# Nodo_actuador_wa4_v1_b.net
KiCad netlist of a schematic drawn in EAGLE
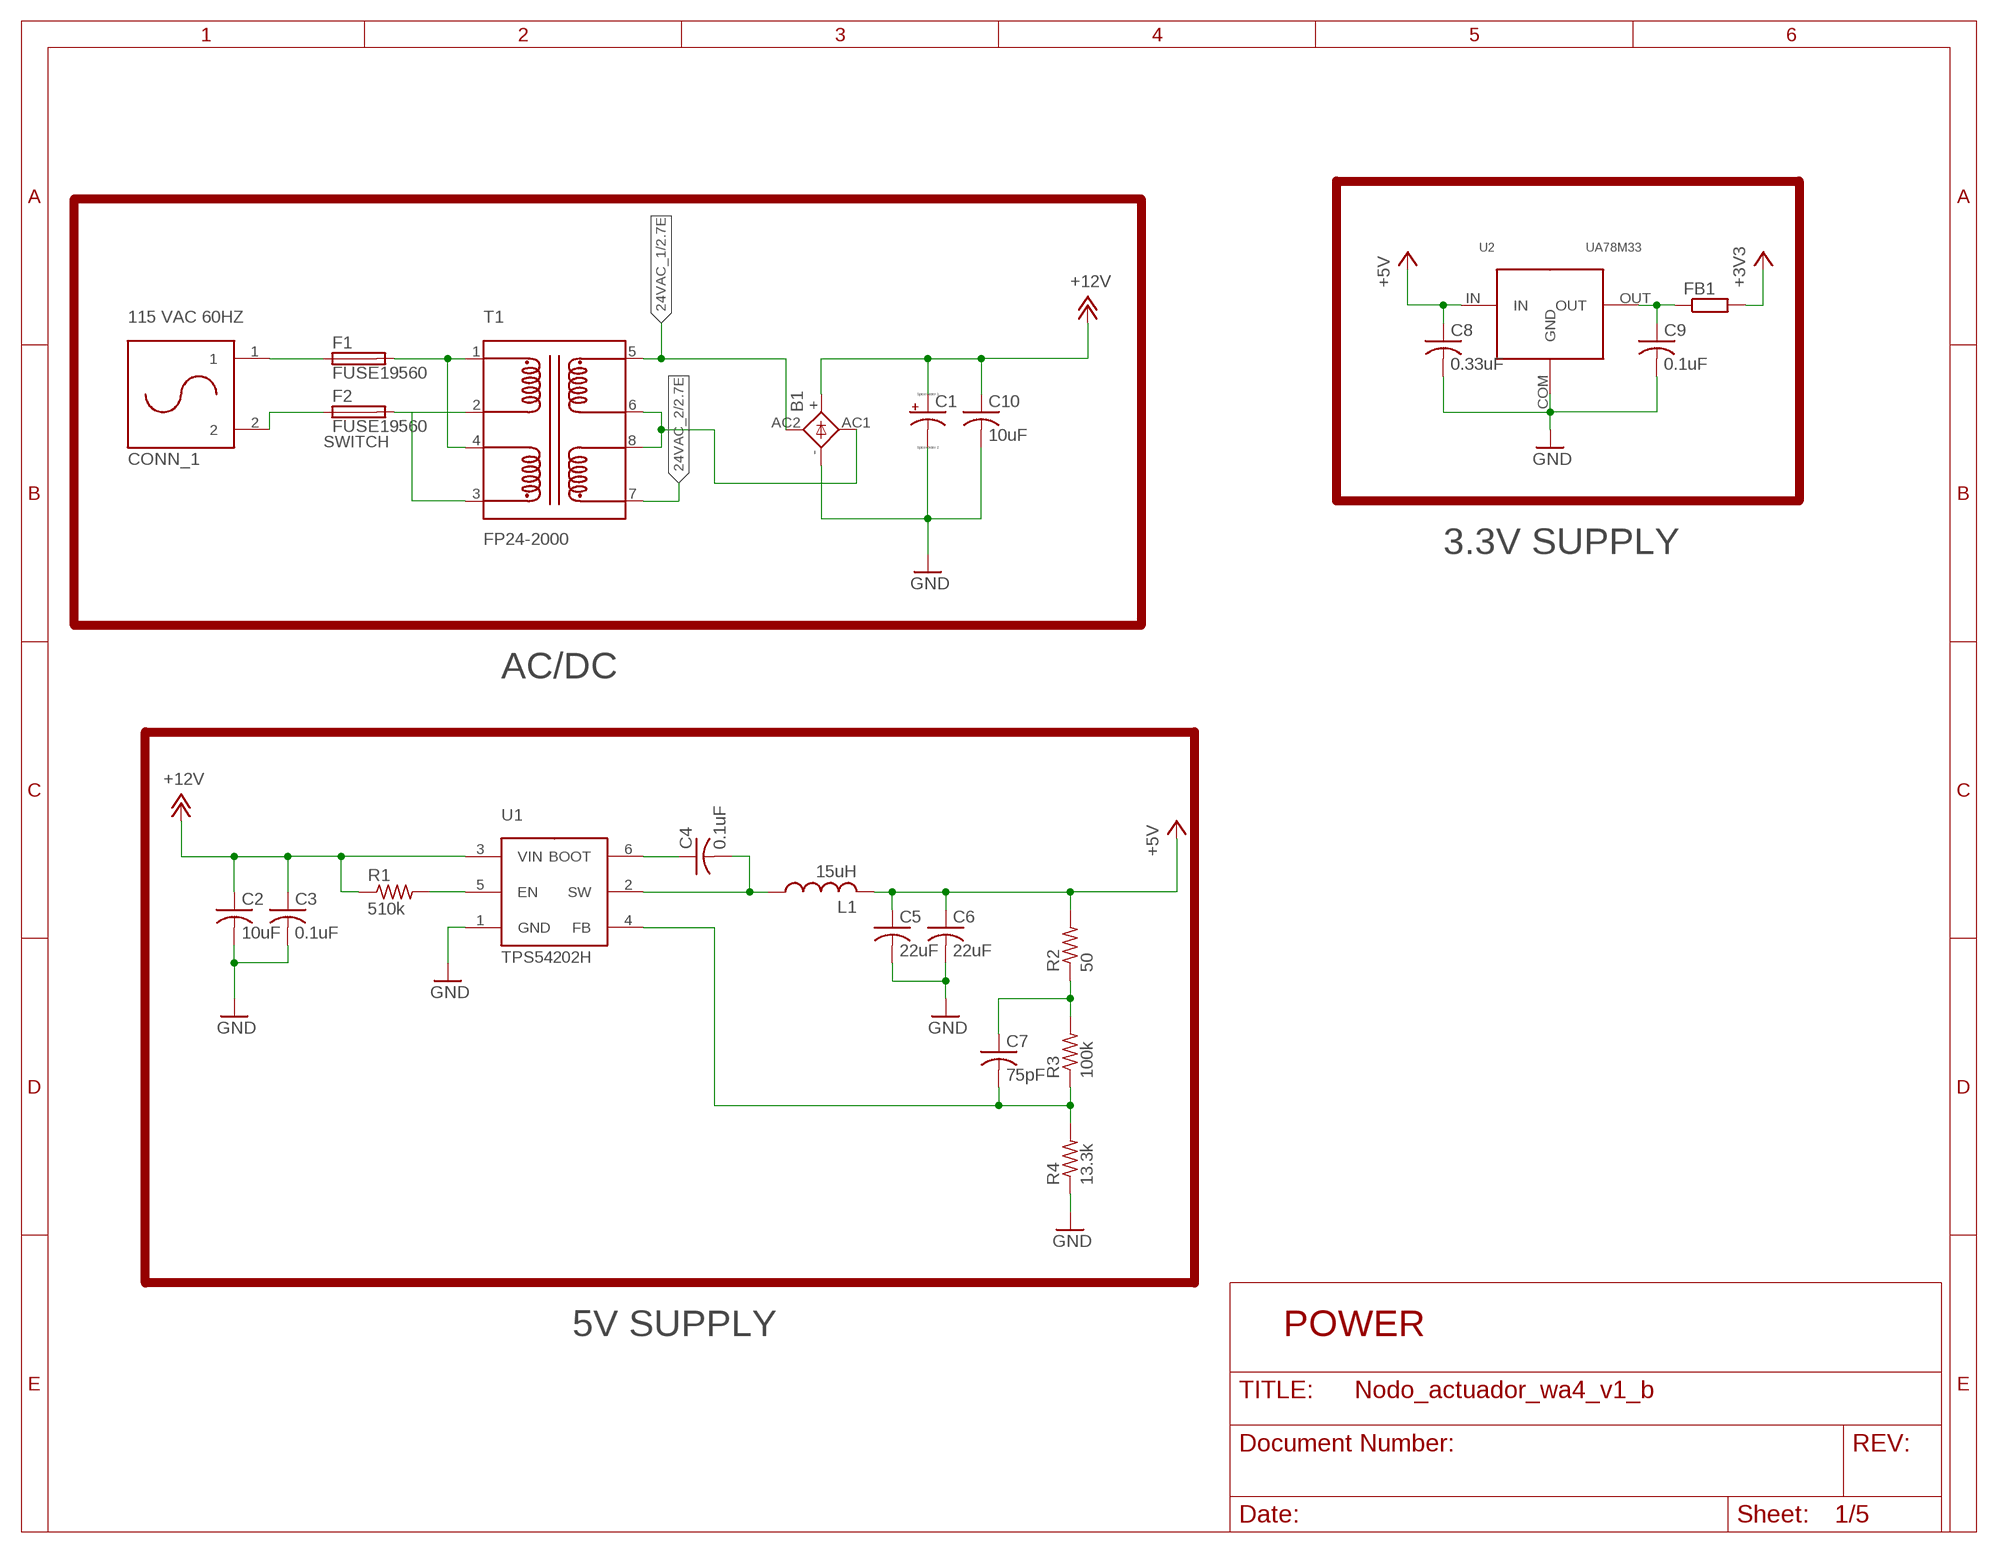
[diagram p0: schematic, sheet 1]
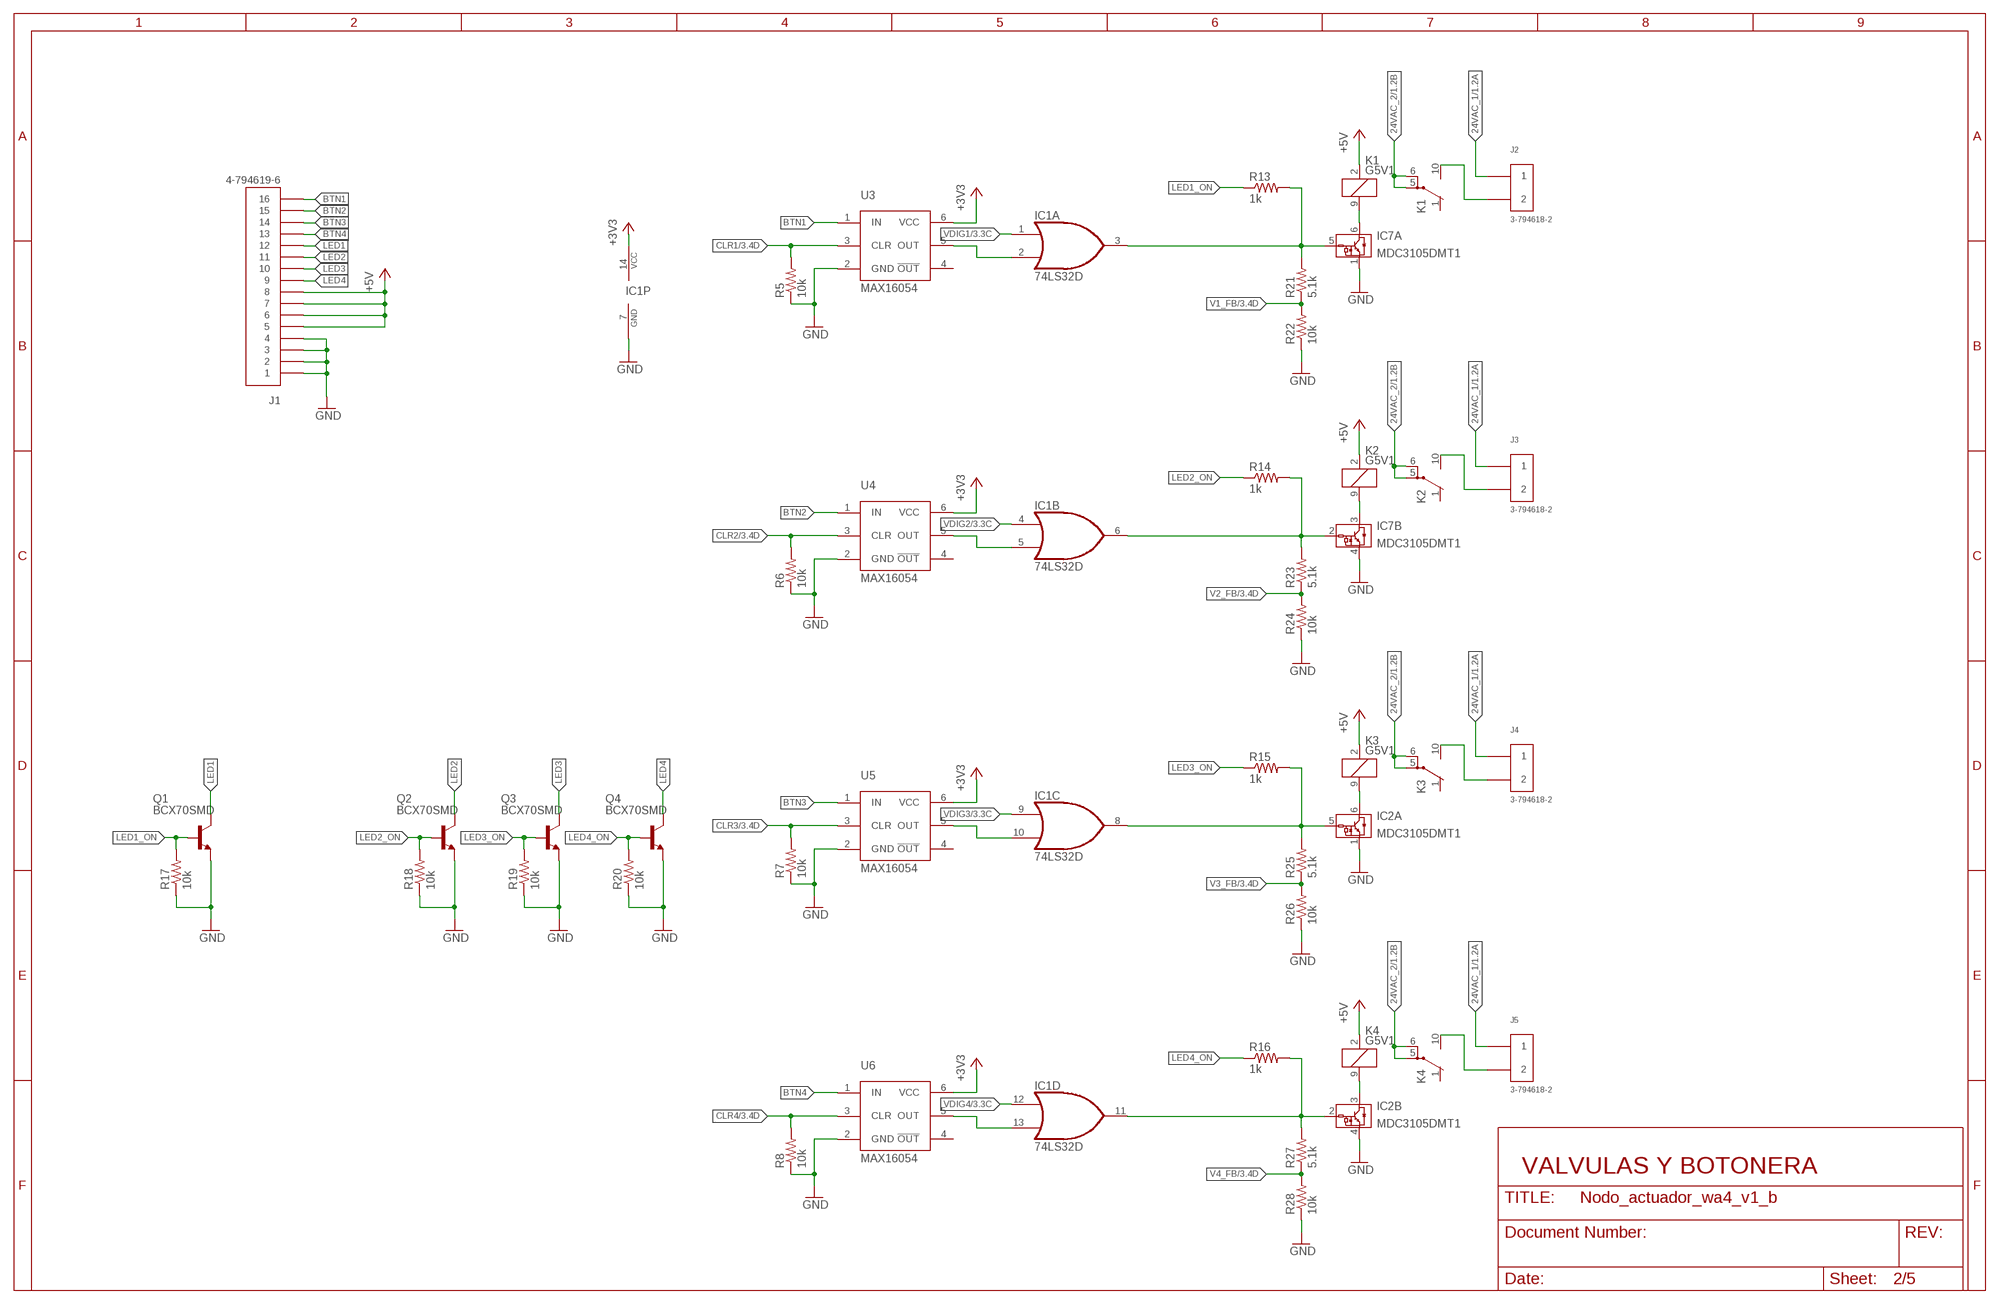
[diagram p1: schematic, sheet 2]
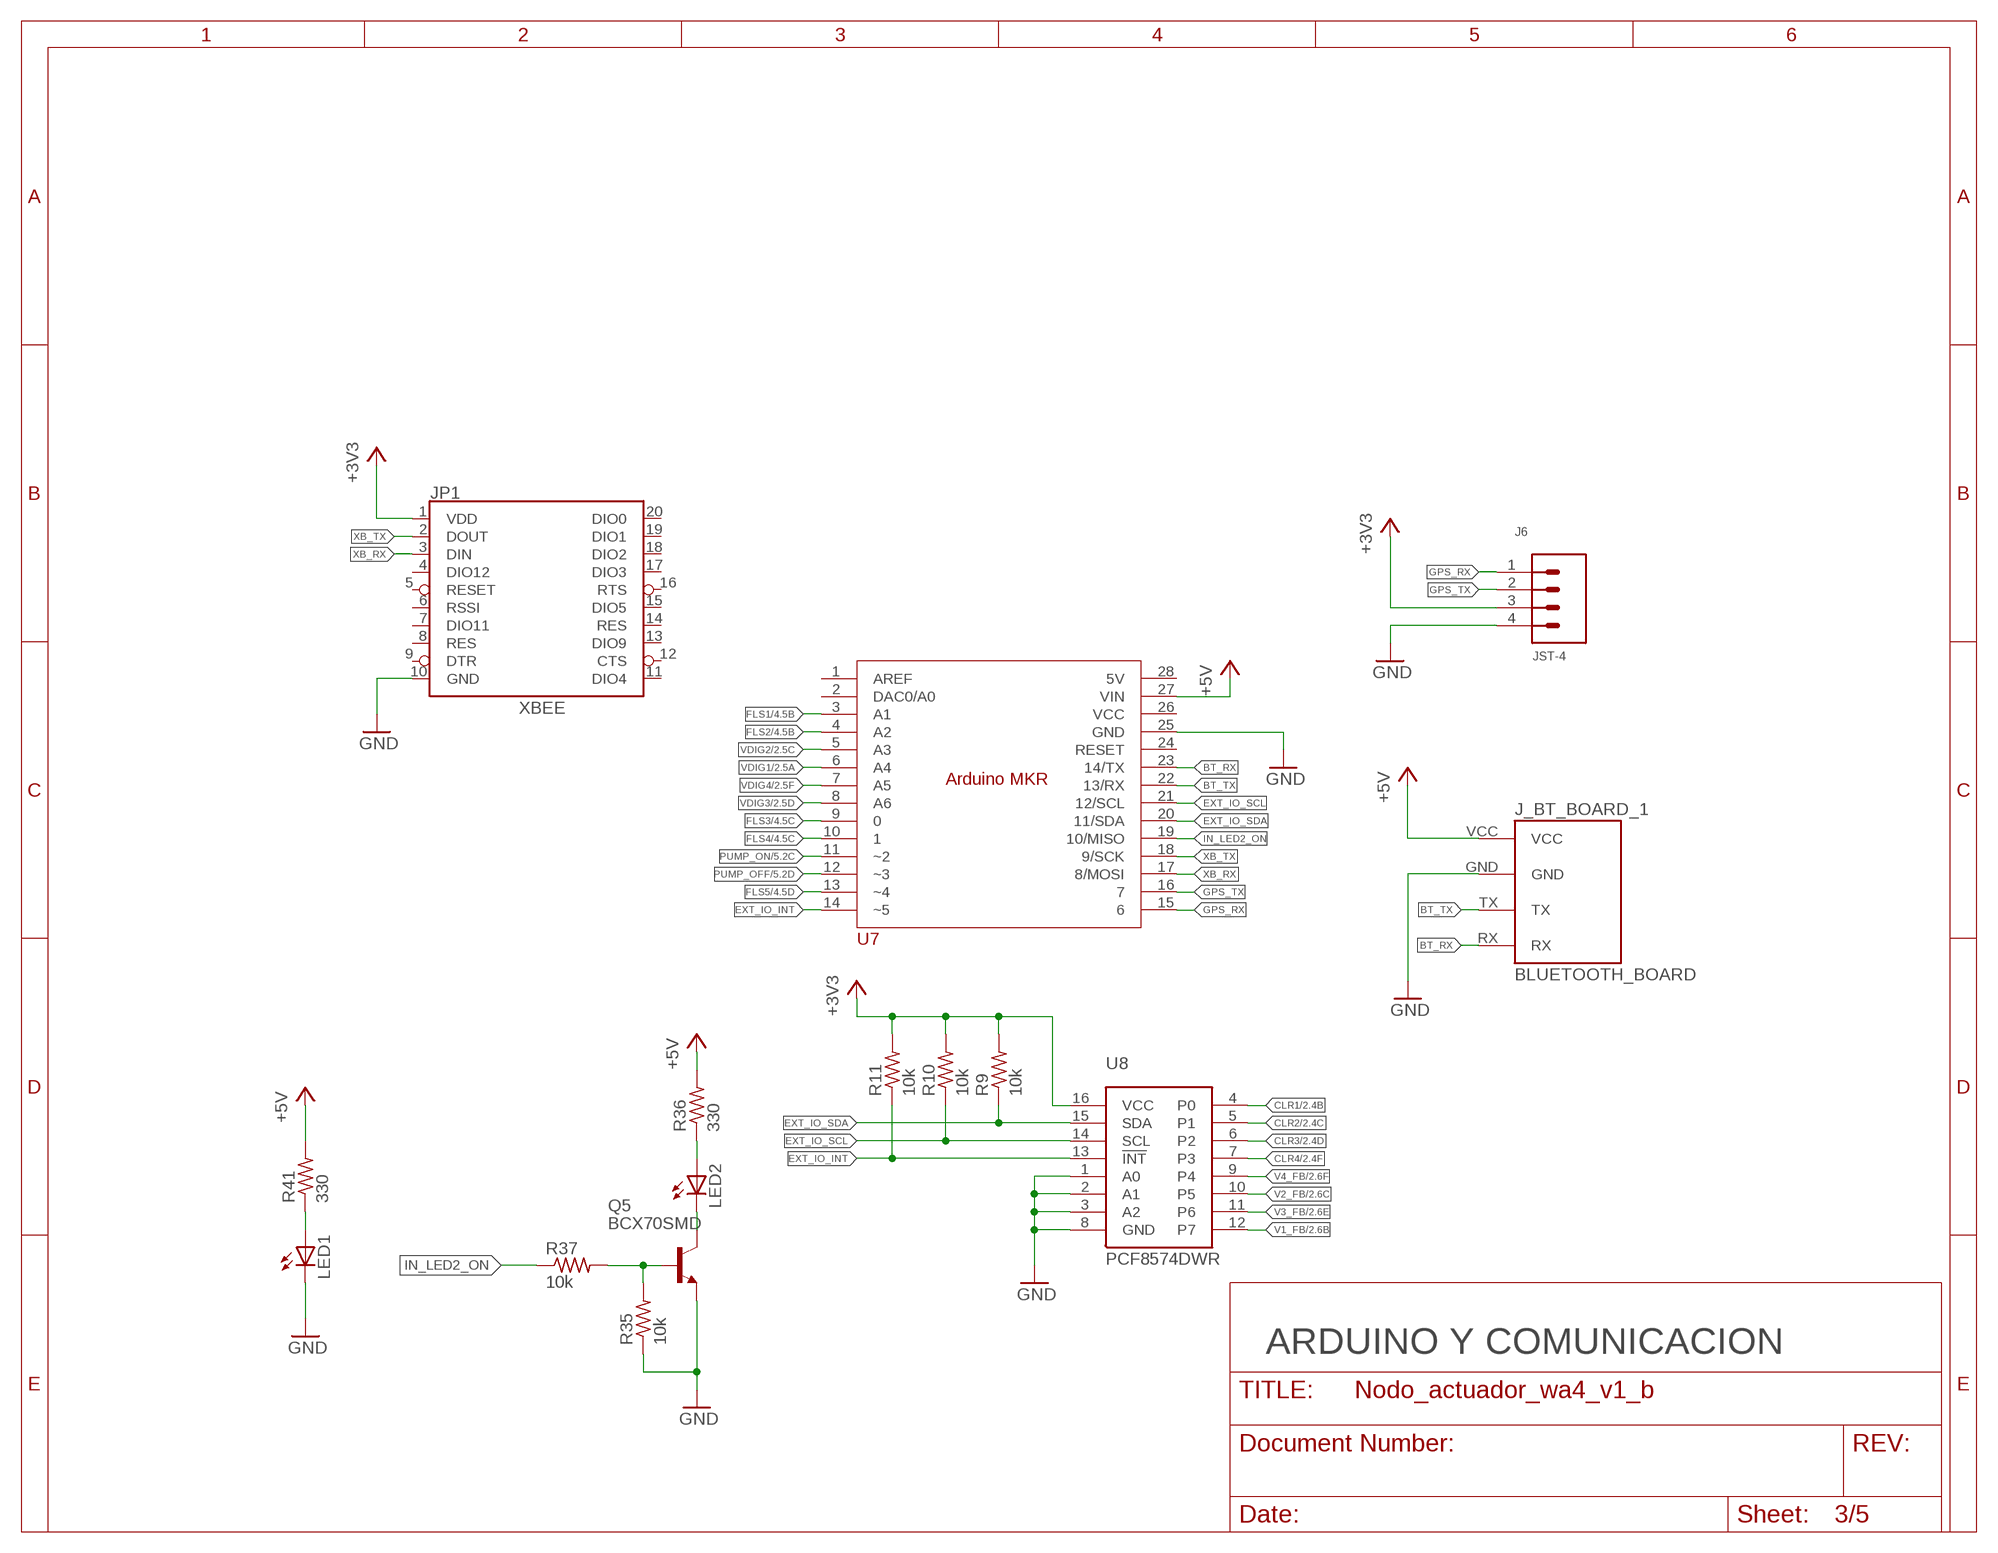
[diagram p2: schematic, sheet 3]
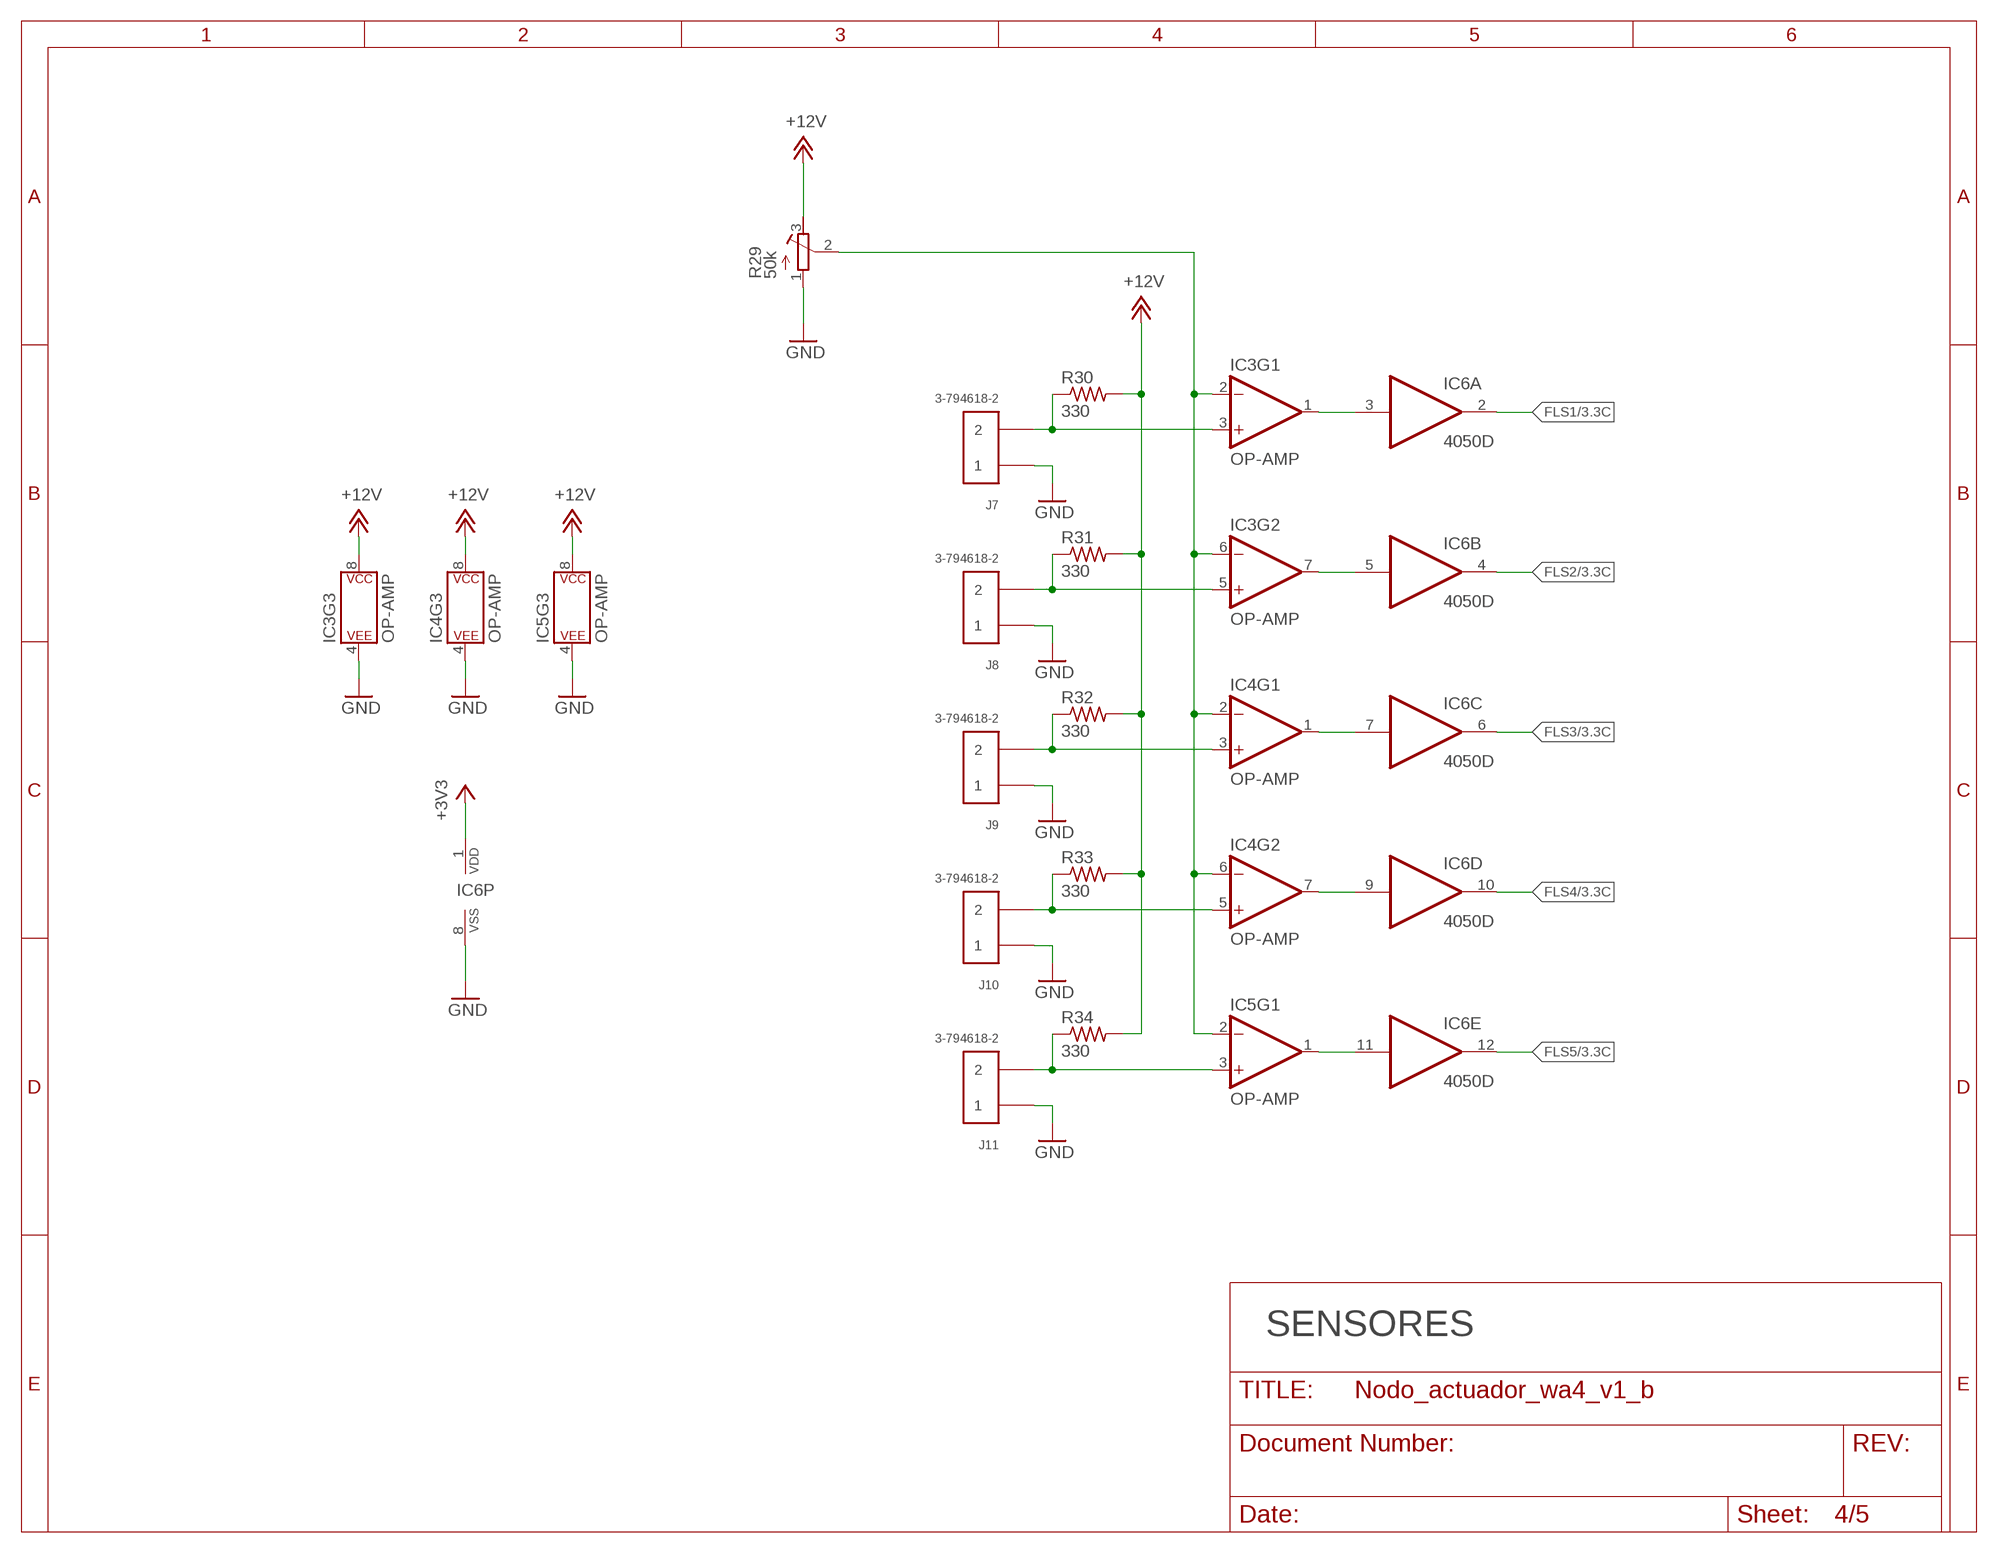
[diagram p3: schematic, sheet 4]
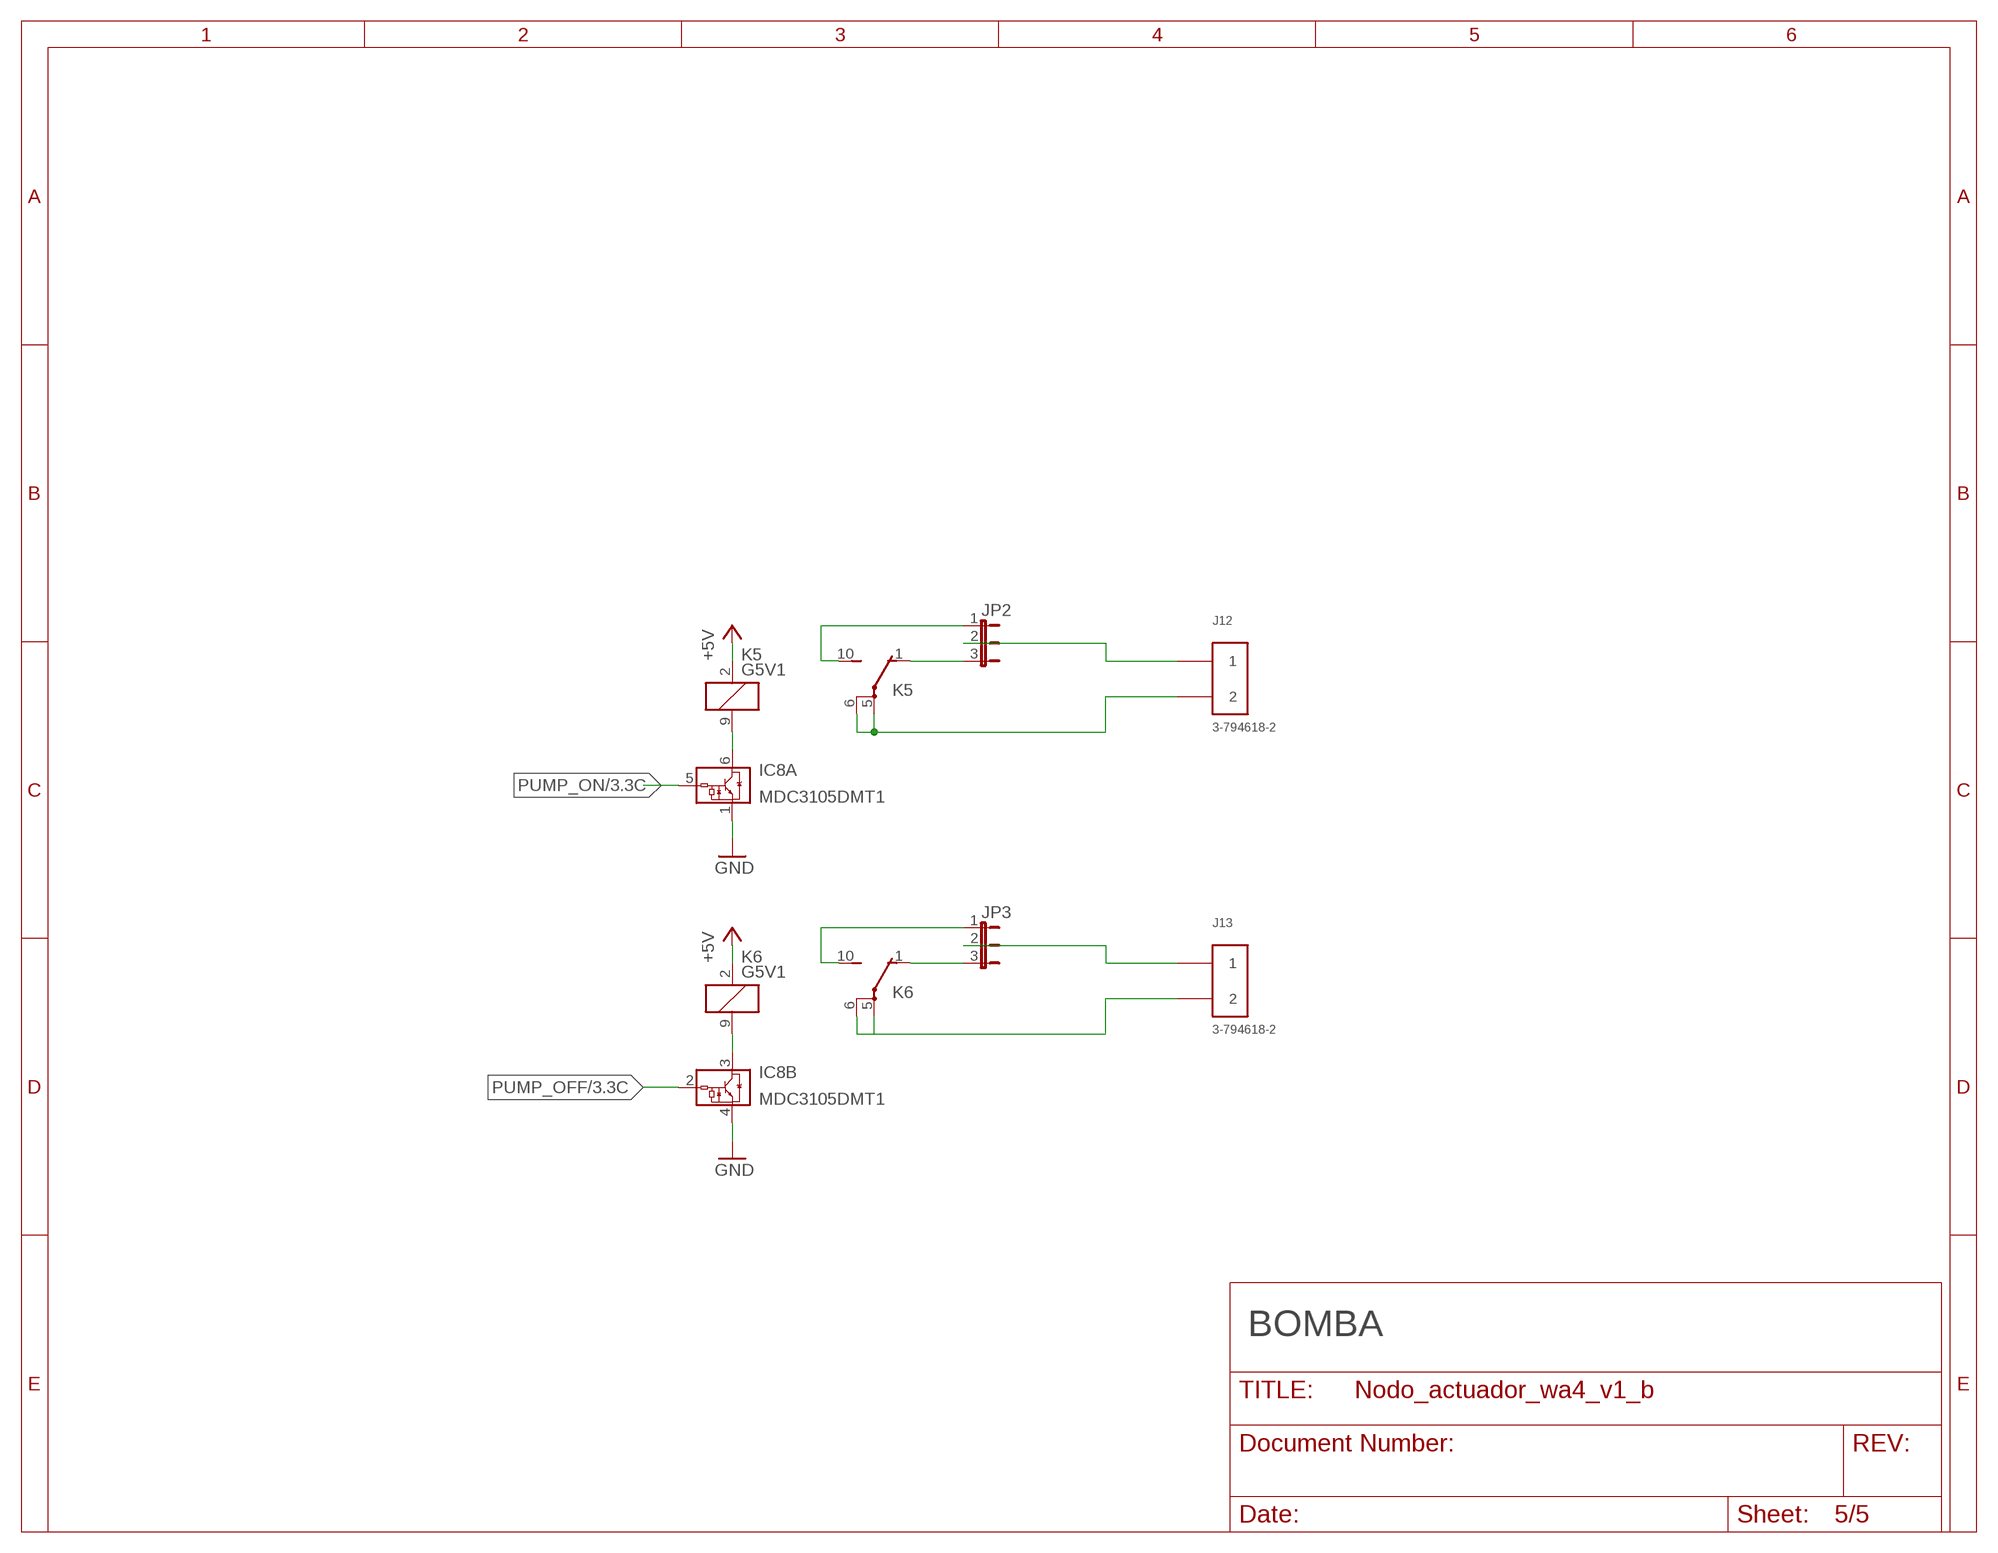
[diagram p4: schematic, sheet 5]

(export (version "E")
  (design (tool "Eeschema 10.0.6"))
  (components
    (comp (ref "IC8")
      (value "MDC3105DMT1")
      (footprint "eagle-import:SC-74")
      (fields (field (name "MPN") "MDC3105DMT1G"))
      (libsource (lib "eagle-import") (part "MDC3105DMT1"))
    )
    (comp (ref "J12")
      (value "3-794618-2")
      (footprint "eagle-import:3-794618-2")
      (libsource (lib "eagle-import") (part "3-794618-2"))
    )
    (comp (ref "J13")
      (value "3-794618-2")
      (footprint "eagle-import:3-794618-2")
      (libsource (lib "eagle-import") (part "3-794618-2"))
    )
    (comp (ref "JP2")
      (value "JP2E")
      (footprint "eagle-import:JP2")
      (libsource (lib "eagle-import") (part "JP2E"))
    )
    (comp (ref "JP3")
      (value "JP2E")
      (footprint "eagle-import:JP2")
      (libsource (lib "eagle-import") (part "JP2E"))
    )
    (comp (ref "K5")
      (value "G5V1")
      (footprint "eagle-import:G5V1")
      (fields (field (name "MPN") "G5V-1-DC24"))
      (libsource (lib "eagle-import") (part "G5V1"))
    )
    (comp (ref "K6")
      (value "G5V1")
      (footprint "eagle-import:G5V1")
      (fields (field (name "MPN") "G5V-1-DC24"))
      (libsource (lib "eagle-import") (part "G5V1"))
    )
    (comp (ref "IC3")
      (value "OP-AMP")
      (footprint "eagle-import:SO08")
      (libsource (lib "eagle-import") (part "OPAMP-DUALU"))
    )
    (comp (ref "IC4")
      (value "OP-AMP")
      (footprint "eagle-import:SO08")
      (libsource (lib "eagle-import") (part "OPAMP-DUALU"))
    )
    (comp (ref "IC5")
      (value "OP-AMP")
      (footprint "eagle-import:SO08")
      (libsource (lib "eagle-import") (part "OPAMP-DUALU"))
    )
    (comp (ref "IC6")
      (value "4050D")
      (footprint "eagle-import:SO16")
      (libsource (lib "eagle-import") (part "4050D"))
    )
    (comp (ref "J7")
      (value "3-794618-2")
      (footprint "eagle-import:3-794618-2")
      (libsource (lib "eagle-import") (part "3-794618-2"))
    )
    (comp (ref "J8")
      (value "3-794618-2")
      (footprint "eagle-import:3-794618-2")
      (libsource (lib "eagle-import") (part "3-794618-2"))
    )
    (comp (ref "J9")
      (value "3-794618-2")
      (footprint "eagle-import:3-794618-2")
      (libsource (lib "eagle-import") (part "3-794618-2"))
    )
    (comp (ref "J10")
      (value "3-794618-2")
      (footprint "eagle-import:3-794618-2")
      (libsource (lib "eagle-import") (part "3-794618-2"))
    )
    (comp (ref "J11")
      (value "3-794618-2")
      (footprint "eagle-import:3-794618-2")
      (libsource (lib "eagle-import") (part "3-794618-2"))
    )
    (comp (ref "R29")
      (value "50k")
      (footprint "eagle-import:RTRIM3224W")
      (libsource (lib "eagle-import") (part "R-TRIMM3224W"))
    )
    (comp (ref "R30")
      (value "330")
      (footprint "eagle-import:R0805")
      (libsource (lib "eagle-import") (part "R-US_R0805"))
    )
    (comp (ref "R31")
      (value "330")
      (footprint "eagle-import:R0805")
      (libsource (lib "eagle-import") (part "R-US_R0805"))
    )
    (comp (ref "R32")
      (value "330")
      (footprint "eagle-import:R0805")
      (libsource (lib "eagle-import") (part "R-US_R0805"))
    )
    (comp (ref "R33")
      (value "330")
      (footprint "eagle-import:R0805")
      (libsource (lib "eagle-import") (part "R-US_R0805"))
    )
    (comp (ref "R34")
      (value "330")
      (footprint "eagle-import:R0805")
      (libsource (lib "eagle-import") (part "R-US_R0805"))
    )
    (comp (ref "B1")
      (value "GBU4")
      (footprint "eagle-import:GBU4S")
      (libsource (lib "eagle-import") (part "GBU4"))
    )
    (comp (ref "C1")
      (value "CPOL-USE5-13")
      (footprint "eagle-import:E5-13")
      (libsource (lib "eagle-import") (part "CPOL-USE5-13"))
    )
    (comp (ref "C2")
      (value "10uF")
      (footprint "eagle-import:C0805")
      (libsource (lib "eagle-import") (part "C-USC0805"))
    )
    (comp (ref "C3")
      (value "0.1uF")
      (footprint "eagle-import:C0805")
      (libsource (lib "eagle-import") (part "C-USC0805"))
    )
    (comp (ref "C4")
      (value "0.1uF")
      (footprint "eagle-import:C0805")
      (libsource (lib "eagle-import") (part "C-USC0805"))
    )
    (comp (ref "C5")
      (value "22uF")
      (footprint "eagle-import:C0805")
      (libsource (lib "eagle-import") (part "C-USC0805"))
    )
    (comp (ref "C6")
      (value "22uF")
      (footprint "eagle-import:C0805")
      (libsource (lib "eagle-import") (part "C-USC0805"))
    )
    (comp (ref "C7")
      (value "75pF")
      (footprint "eagle-import:C0805")
      (libsource (lib "eagle-import") (part "C-USC0805"))
    )
    (comp (ref "C8")
      (value "0.33uF")
      (footprint "eagle-import:C0805")
      (libsource (lib "eagle-import") (part "C-USC0805"))
    )
    (comp (ref "C9")
      (value "0.1uF")
      (footprint "eagle-import:C0805")
      (libsource (lib "eagle-import") (part "C-USC0805"))
    )
    (comp (ref "C10")
      (value "10uF")
      (footprint "eagle-import:C0805")
      (libsource (lib "eagle-import") (part "C-USC0805"))
    )
    (comp (ref "CONN_1")
      (value "115 VAC 60HZ")
      (footprint "eagle-import:2570-2210")
      (libsource (lib "eagle-import") (part "2570-2210"))
    )
    (comp (ref "F1")
      (value "FUSE19560")
      (footprint "eagle-import:19560")
      (fields (field (name "MPN") "56000001009"))
      (libsource (lib "eagle-import") (part "FUSE19560"))
    )
    (comp (ref "F2")
      (value "FUSE19560")
      (footprint "eagle-import:19560")
      (fields (field (name "MPN") "56000001009"))
      (libsource (lib "eagle-import") (part "FUSE19560"))
    )
    (comp (ref "FB1")
      (value "R-EU_M0805")
      (footprint "eagle-import:M0805")
      (libsource (lib "eagle-import") (part "R-EU_M0805"))
    )
    (comp (ref "L1")
      (value "15uH")
      (footprint "eagle-import:VLS5045")
      (libsource (lib "eagle-import") (part "VLS5045EX"))
    )
    (comp (ref "R1")
      (value "510k")
      (footprint "eagle-import:R0805")
      (libsource (lib "eagle-import") (part "R-US_R0805"))
    )
    (comp (ref "R2")
      (value "50")
      (footprint "eagle-import:R0805")
      (libsource (lib "eagle-import") (part "R-US_R0805"))
    )
    (comp (ref "R3")
      (value "100k")
      (footprint "eagle-import:R0805")
      (libsource (lib "eagle-import") (part "R-US_R0805"))
    )
    (comp (ref "R4")
      (value "13.3k")
      (footprint "eagle-import:R0805")
      (libsource (lib "eagle-import") (part "R-US_R0805"))
    )
    (comp (ref "T1")
      (value "FP24-2000")
      (footprint "eagle-import:FP24-2000")
      (libsource (lib "eagle-import") (part "FP24-2000"))
    )
    (comp (ref "U1")
      (value "TPS54202H")
      (footprint "eagle-import:SOT-23-6")
      (libsource (lib "eagle-import") (part "TPS54202H"))
    )
    (comp (ref "U2")
      (value "UA78M33")
      (footprint "eagle-import:UA78XX")
      (libsource (lib "eagle-import") (part "UA78M33"))
    )
    (comp (ref "J6")
      (value "JST-4")
      (footprint "eagle-import:JST-4")
      (libsource (lib "eagle-import") (part "JST-4"))
    )
    (comp (ref "JP1")
      (value "XBEESILK")
      (footprint "eagle-import:XBEE-SILK")
      (libsource (lib "eagle-import") (part "XBEESILK"))
    )
    (comp (ref "J_BT_BOARD_1")
      (value "BLUETOOTH_BOARD")
      (footprint "eagle-import:BT_BOARD_FOOTPRINT")
      (libsource (lib "eagle-import") (part "BLUETOOTH_BOARD"))
    )
    (comp (ref "LED1")
      (value "LEDCHIP-LED0805")
      (footprint "eagle-import:CHIP-LED0805")
      (libsource (lib "eagle-import") (part "LEDCHIP-LED0805"))
    )
    (comp (ref "LED2")
      (value "LEDCHIP-LED0805")
      (footprint "eagle-import:CHIP-LED0805")
      (libsource (lib "eagle-import") (part "LEDCHIP-LED0805"))
    )
    (comp (ref "Q5")
      (value "BCX70SMD")
      (footprint "eagle-import:SOT23")
      (libsource (lib "eagle-import") (part "BCX70SMD"))
    )
    (comp (ref "R9")
      (value "10k")
      (footprint "eagle-import:R0805")
      (libsource (lib "eagle-import") (part "R-US_R0805"))
    )
    (comp (ref "R10")
      (value "10k")
      (footprint "eagle-import:R0805")
      (libsource (lib "eagle-import") (part "R-US_R0805"))
    )
    (comp (ref "R11")
      (value "10k")
      (footprint "eagle-import:R0805")
      (libsource (lib "eagle-import") (part "R-US_R0805"))
    )
    (comp (ref "R35")
      (value "10k")
      (footprint "eagle-import:R0805")
      (libsource (lib "eagle-import") (part "R-US_R0805"))
    )
    (comp (ref "R36")
      (value "330")
      (footprint "eagle-import:R0805")
      (libsource (lib "eagle-import") (part "R-US_R0805"))
    )
    (comp (ref "R37")
      (value "10k")
      (footprint "eagle-import:R0805")
      (libsource (lib "eagle-import") (part "R-US_R0805"))
    )
    (comp (ref "R41")
      (value "330")
      (footprint "eagle-import:R0805")
      (libsource (lib "eagle-import") (part "R-US_R0805"))
    )
    (comp (ref "U7")
      (value "ARDUINO_MKR")
      (footprint "eagle-import:ARDUINO_MKR")
      (libsource (lib "eagle-import") (part "ARDUINO_MKR"))
    )
    (comp (ref "U8")
      (value "PCF8574DWR")
      (footprint "eagle-import:SOIC16_1")
      (libsource (lib "eagle-import") (part "PCF8574DWR"))
    )
    (comp (ref "IC1")
      (value "74LS32D")
      (footprint "eagle-import:SO14")
      (libsource (lib "eagle-import") (part "7432DLS"))
    )
    (comp (ref "IC2")
      (value "MDC3105DMT1")
      (footprint "eagle-import:SC-74")
      (fields (field (name "MPN") "MDC3105DMT1G"))
      (libsource (lib "eagle-import") (part "MDC3105DMT1"))
    )
    (comp (ref "IC7")
      (value "MDC3105DMT1")
      (footprint "eagle-import:SC-74")
      (fields (field (name "MPN") "MDC3105DMT1G"))
      (libsource (lib "eagle-import") (part "MDC3105DMT1"))
    )
    (comp (ref "J1")
      (value "4-794619-6")
      (footprint "eagle-import:4-794619-6")
      (libsource (lib "eagle-import") (part "4-794619-6"))
    )
    (comp (ref "J2")
      (value "3-794618-2")
      (footprint "eagle-import:3-794618-2")
      (libsource (lib "eagle-import") (part "3-794618-2"))
    )
    (comp (ref "J3")
      (value "3-794618-2")
      (footprint "eagle-import:3-794618-2")
      (libsource (lib "eagle-import") (part "3-794618-2"))
    )
    (comp (ref "J4")
      (value "3-794618-2")
      (footprint "eagle-import:3-794618-2")
      (libsource (lib "eagle-import") (part "3-794618-2"))
    )
    (comp (ref "J5")
      (value "3-794618-2")
      (footprint "eagle-import:3-794618-2")
      (libsource (lib "eagle-import") (part "3-794618-2"))
    )
    (comp (ref "K1")
      (value "G5V1")
      (footprint "eagle-import:G5V1")
      (fields (field (name "MPN") "G5V-1-DC24"))
      (libsource (lib "eagle-import") (part "G5V1"))
    )
    (comp (ref "K2")
      (value "G5V1")
      (footprint "eagle-import:G5V1")
      (fields (field (name "MPN") "G5V-1-DC24"))
      (libsource (lib "eagle-import") (part "G5V1"))
    )
    (comp (ref "K3")
      (value "G5V1")
      (footprint "eagle-import:G5V1")
      (fields (field (name "MPN") "G5V-1-DC24"))
      (libsource (lib "eagle-import") (part "G5V1"))
    )
    (comp (ref "K4")
      (value "G5V1")
      (footprint "eagle-import:G5V1")
      (fields (field (name "MPN") "G5V-1-DC24"))
      (libsource (lib "eagle-import") (part "G5V1"))
    )
    (comp (ref "Q1")
      (value "BCX70SMD")
      (footprint "eagle-import:SOT23")
      (libsource (lib "eagle-import") (part "BCX70SMD"))
    )
    (comp (ref "Q2")
      (value "BCX70SMD")
      (footprint "eagle-import:SOT23")
      (libsource (lib "eagle-import") (part "BCX70SMD"))
    )
    (comp (ref "Q3")
      (value "BCX70SMD")
      (footprint "eagle-import:SOT23")
      (libsource (lib "eagle-import") (part "BCX70SMD"))
    )
    (comp (ref "Q4")
      (value "BCX70SMD")
      (footprint "eagle-import:SOT23")
      (libsource (lib "eagle-import") (part "BCX70SMD"))
    )
    (comp (ref "R5")
      (value "10k")
      (footprint "eagle-import:R0805")
      (libsource (lib "eagle-import") (part "R-US_R0805"))
    )
    (comp (ref "R6")
      (value "10k")
      (footprint "eagle-import:R0805")
      (libsource (lib "eagle-import") (part "R-US_R0805"))
    )
    (comp (ref "R7")
      (value "10k")
      (footprint "eagle-import:R0805")
      (libsource (lib "eagle-import") (part "R-US_R0805"))
    )
    (comp (ref "R8")
      (value "10k")
      (footprint "eagle-import:R0805")
      (libsource (lib "eagle-import") (part "R-US_R0805"))
    )
    (comp (ref "R13")
      (value "1k")
      (footprint "eagle-import:R0805")
      (libsource (lib "eagle-import") (part "R-US_R0805"))
    )
    (comp (ref "R14")
      (value "1k")
      (footprint "eagle-import:R0805")
      (libsource (lib "eagle-import") (part "R-US_R0805"))
    )
    (comp (ref "R15")
      (value "1k")
      (footprint "eagle-import:R0805")
      (libsource (lib "eagle-import") (part "R-US_R0805"))
    )
    (comp (ref "R16")
      (value "1k")
      (footprint "eagle-import:R0805")
      (libsource (lib "eagle-import") (part "R-US_R0805"))
    )
    (comp (ref "R17")
      (value "10k")
      (footprint "eagle-import:R0805")
      (libsource (lib "eagle-import") (part "R-US_R0805"))
    )
    (comp (ref "R18")
      (value "10k")
      (footprint "eagle-import:R0805")
      (libsource (lib "eagle-import") (part "R-US_R0805"))
    )
    (comp (ref "R19")
      (value "10k")
      (footprint "eagle-import:R0805")
      (libsource (lib "eagle-import") (part "R-US_R0805"))
    )
    (comp (ref "R20")
      (value "10k")
      (footprint "eagle-import:R0805")
      (libsource (lib "eagle-import") (part "R-US_R0805"))
    )
    (comp (ref "R21")
      (value "5.1k")
      (footprint "eagle-import:R0805")
      (libsource (lib "eagle-import") (part "R-US_R0805"))
    )
    (comp (ref "R22")
      (value "10k")
      (footprint "eagle-import:R0805")
      (libsource (lib "eagle-import") (part "R-US_R0805"))
    )
    (comp (ref "R23")
      (value "5.1k")
      (footprint "eagle-import:R0805")
      (libsource (lib "eagle-import") (part "R-US_R0805"))
    )
    (comp (ref "R24")
      (value "10k")
      (footprint "eagle-import:R0805")
      (libsource (lib "eagle-import") (part "R-US_R0805"))
    )
    (comp (ref "R25")
      (value "5.1k")
      (footprint "eagle-import:R0805")
      (libsource (lib "eagle-import") (part "R-US_R0805"))
    )
    (comp (ref "R26")
      (value "10k")
      (footprint "eagle-import:R0805")
      (libsource (lib "eagle-import") (part "R-US_R0805"))
    )
    (comp (ref "R27")
      (value "5.1k")
      (footprint "eagle-import:R0805")
      (libsource (lib "eagle-import") (part "R-US_R0805"))
    )
    (comp (ref "R28")
      (value "10k")
      (footprint "eagle-import:R0805")
      (libsource (lib "eagle-import") (part "R-US_R0805"))
    )
    (comp (ref "U3")
      (value "MAX16054")
      (footprint "eagle-import:SOT-23-6")
      (libsource (lib "eagle-import") (part "MAX16054"))
    )
    (comp (ref "U4")
      (value "MAX16054")
      (footprint "eagle-import:SOT-23-6")
      (libsource (lib "eagle-import") (part "MAX16054"))
    )
    (comp (ref "U5")
      (value "MAX16054")
      (footprint "eagle-import:SOT-23-6")
      (libsource (lib "eagle-import") (part "MAX16054"))
    )
    (comp (ref "U6")
      (value "MAX16054")
      (footprint "eagle-import:SOT-23-6")
      (libsource (lib "eagle-import") (part "MAX16054"))
    )
  )
  (nets
    (net (code "1") (name "+3V3") (class "Default")
      (node (ref "FB1") (pin "2") (pinfunction "2_2") (pintype "passive"))
      (node (ref "IC1") (pin "14") (pinfunction "VCC_14") (pintype "power_in"))
      (node (ref "IC6") (pin "1") (pinfunction "VDD_1") (pintype "power_in"))
      (node (ref "J6") (pin "3") (pinfunction "3_3") (pintype "bidirectional"))
      (node (ref "JP1") (pin "1") (pinfunction "VDD_1") (pintype "power_in"))
      (node (ref "R10") (pin "2") (pinfunction "2_2") (pintype "passive"))
      (node (ref "R11") (pin "2") (pinfunction "2_2") (pintype "passive"))
      (node (ref "R9") (pin "2") (pinfunction "2_2") (pintype "passive"))
      (node (ref "U3") (pin "6") (pinfunction "VCC_6") (pintype "bidirectional"))
      (node (ref "U4") (pin "6") (pinfunction "VCC_6") (pintype "bidirectional"))
      (node (ref "U5") (pin "6") (pinfunction "VCC_6") (pintype "bidirectional"))
      (node (ref "U6") (pin "6") (pinfunction "VCC_6") (pintype "bidirectional"))
      (node (ref "U8") (pin "16") (pinfunction "VCC_16") (pintype "bidirectional"))
    )
    (net (code "2") (name "+5V") (class "Default")
      (node (ref "C5") (pin "1") (pinfunction "1_1") (pintype "passive"))
      (node (ref "C6") (pin "1") (pinfunction "1_1") (pintype "passive"))
      (node (ref "C8") (pin "1") (pinfunction "1_1") (pintype "passive"))
      (node (ref "J1") (pin "5") (pinfunction "5_5") (pintype "bidirectional"))
      (node (ref "J1") (pin "6") (pinfunction "6_6") (pintype "bidirectional"))
      (node (ref "J1") (pin "7") (pinfunction "7_7") (pintype "bidirectional"))
      (node (ref "J1") (pin "8") (pinfunction "8_8") (pintype "bidirectional"))
      (node (ref "J_BT_BOARD_1") (pin "VCC") (pinfunction "VCC_VCC") (pintype "bidirectional"))
      (node (ref "K1") (pin "2") (pinfunction "1_2") (pintype "passive"))
      (node (ref "K2") (pin "2") (pinfunction "1_2") (pintype "passive"))
      (node (ref "K3") (pin "2") (pinfunction "1_2") (pintype "passive"))
      (node (ref "K4") (pin "2") (pinfunction "1_2") (pintype "passive"))
      (node (ref "K5") (pin "2") (pinfunction "1_2") (pintype "passive"))
      (node (ref "K6") (pin "2") (pinfunction "1_2") (pintype "passive"))
      (node (ref "L1") (pin "2") (pinfunction "2_2") (pintype "passive"))
      (node (ref "R2") (pin "2") (pinfunction "2_2") (pintype "passive"))
      (node (ref "R36") (pin "2") (pinfunction "2_2") (pintype "passive"))
      (node (ref "R41") (pin "2") (pinfunction "2_2") (pintype "passive"))
      (node (ref "U2") (pin "IN") (pinfunction "IN_IN") (pintype "bidirectional"))
      (node (ref "U7") (pin "27") (pinfunction "VIN_27") (pintype "bidirectional"))
    )
    (net (code "3") (name "+12V") (class "Default")
      (node (ref "B1") (pin "+") (pinfunction "+_+") (pintype "passive"))
      (node (ref "C1") (pin "+") (pinfunction "+_+") (pintype "passive"))
      (node (ref "C10") (pin "1") (pinfunction "1_1") (pintype "passive"))
      (node (ref "C2") (pin "1") (pinfunction "1_1") (pintype "passive"))
      (node (ref "C3") (pin "1") (pinfunction "1_1") (pintype "passive"))
      (node (ref "IC3") (pin "8") (pinfunction "P$V+_8") (pintype "bidirectional"))
      (node (ref "IC4") (pin "8") (pinfunction "P$V+_8") (pintype "bidirectional"))
      (node (ref "IC5") (pin "8") (pinfunction "P$V+_8") (pintype "bidirectional"))
      (node (ref "R1") (pin "1") (pinfunction "1_1") (pintype "passive"))
      (node (ref "R29") (pin "3") (pinfunction "E_3") (pintype "passive"))
      (node (ref "R30") (pin "2") (pinfunction "2_2") (pintype "passive"))
      (node (ref "R31") (pin "2") (pinfunction "2_2") (pintype "passive"))
      (node (ref "R32") (pin "2") (pinfunction "2_2") (pintype "passive"))
      (node (ref "R33") (pin "2") (pinfunction "2_2") (pintype "passive"))
      (node (ref "R34") (pin "2") (pinfunction "2_2") (pintype "passive"))
      (node (ref "U1") (pin "3") (pinfunction "VIN_3") (pintype "bidirectional"))
    )
    (net (code "4") (name "24VAC_1") (class "Default")
      (node (ref "B1") (pin "AC2") (pinfunction "AC1_AC2") (pintype "passive"))
      (node (ref "J2") (pin "1") (pinfunction "1_1") (pintype "bidirectional"))
      (node (ref "J3") (pin "1") (pinfunction "1_1") (pintype "bidirectional"))
      (node (ref "J4") (pin "1") (pinfunction "1_1") (pintype "bidirectional"))
      (node (ref "J5") (pin "1") (pinfunction "1_1") (pintype "bidirectional"))
      (node (ref "T1") (pin "5") (pinfunction "5_5") (pintype "passive"))
    )
    (net (code "5") (name "24VAC_2") (class "Default")
      (node (ref "K1") (pin "5") (pinfunction "P_5") (pintype "passive"))
      (node (ref "K1") (pin "6") (pinfunction "P_6") (pintype "passive"))
      (node (ref "K2") (pin "5") (pinfunction "P_5") (pintype "passive"))
      (node (ref "K2") (pin "6") (pinfunction "P_6") (pintype "passive"))
      (node (ref "K3") (pin "5") (pinfunction "P_5") (pintype "passive"))
      (node (ref "K3") (pin "6") (pinfunction "P_6") (pintype "passive"))
      (node (ref "K4") (pin "5") (pinfunction "P_5") (pintype "passive"))
      (node (ref "K4") (pin "6") (pinfunction "P_6") (pintype "passive"))
      (node (ref "T1") (pin "7") (pinfunction "7_7") (pintype "passive"))
    )
    (net (code "6") (name "BTN1") (class "Default")
      (node (ref "J1") (pin "16") (pinfunction "16_16") (pintype "bidirectional"))
      (node (ref "U3") (pin "1") (pinfunction "IN_1") (pintype "bidirectional"))
    )
    (net (code "7") (name "BTN2") (class "Default")
      (node (ref "J1") (pin "15") (pinfunction "15_15") (pintype "bidirectional"))
      (node (ref "U4") (pin "1") (pinfunction "IN_1") (pintype "bidirectional"))
    )
    (net (code "8") (name "BTN3") (class "Default")
      (node (ref "J1") (pin "14") (pinfunction "14_14") (pintype "bidirectional"))
      (node (ref "U5") (pin "1") (pinfunction "IN_1") (pintype "bidirectional"))
    )
    (net (code "9") (name "BTN4") (class "Default")
      (node (ref "J1") (pin "13") (pinfunction "13_13") (pintype "bidirectional"))
      (node (ref "U6") (pin "1") (pinfunction "IN_1") (pintype "bidirectional"))
    )
    (net (code "10") (name "BT_RX") (class "Default")
      (node (ref "J_BT_BOARD_1") (pin "RX") (pinfunction "RX_RX") (pintype "bidirectional"))
      (node (ref "U7") (pin "23") (pinfunction "14/TX_23") (pintype "bidirectional"))
    )
    (net (code "11") (name "BT_TX") (class "Default")
      (node (ref "J_BT_BOARD_1") (pin "TX") (pinfunction "TX_TX") (pintype "bidirectional"))
      (node (ref "U7") (pin "22") (pinfunction "13/RX_22") (pintype "bidirectional"))
    )
    (net (code "12") (name "CLR1") (class "Default")
      (node (ref "R5") (pin "2") (pinfunction "2_2") (pintype "passive"))
      (node (ref "U3") (pin "3") (pinfunction "CLR_3") (pintype "bidirectional"))
      (node (ref "U8") (pin "4") (pinfunction "P0_4") (pintype "bidirectional"))
    )
    (net (code "13") (name "CLR2") (class "Default")
      (node (ref "R6") (pin "2") (pinfunction "2_2") (pintype "passive"))
      (node (ref "U4") (pin "3") (pinfunction "CLR_3") (pintype "bidirectional"))
      (node (ref "U8") (pin "5") (pinfunction "P1_5") (pintype "bidirectional"))
    )
    (net (code "14") (name "CLR3") (class "Default")
      (node (ref "R7") (pin "2") (pinfunction "2_2") (pintype "passive"))
      (node (ref "U5") (pin "3") (pinfunction "CLR_3") (pintype "bidirectional"))
      (node (ref "U8") (pin "6") (pinfunction "P2_6") (pintype "bidirectional"))
    )
    (net (code "15") (name "CLR4") (class "Default")
      (node (ref "R8") (pin "2") (pinfunction "2_2") (pintype "passive"))
      (node (ref "U6") (pin "3") (pinfunction "CLR_3") (pintype "bidirectional"))
      (node (ref "U8") (pin "7") (pinfunction "P3_7") (pintype "bidirectional"))
    )
    (net (code "16") (name "EXT_IO_INT") (class "Default")
      (node (ref "R11") (pin "1") (pinfunction "1_1") (pintype "passive"))
      (node (ref "U7") (pin "14") (pinfunction "~{5}_14") (pintype "bidirectional"))
      (node (ref "U8") (pin "13") (pinfunction "~{INT}_13") (pintype "bidirectional"))
    )
    (net (code "17") (name "EXT_IO_SCL") (class "Default")
      (node (ref "R10") (pin "1") (pinfunction "1_1") (pintype "passive"))
      (node (ref "U7") (pin "21") (pinfunction "12/SCL_21") (pintype "bidirectional"))
      (node (ref "U8") (pin "14") (pinfunction "SCL_14") (pintype "bidirectional"))
    )
    (net (code "18") (name "EXT_IO_SDA") (class "Default")
      (node (ref "R9") (pin "1") (pinfunction "1_1") (pintype "passive"))
      (node (ref "U7") (pin "20") (pinfunction "11/SDA_20") (pintype "bidirectional"))
      (node (ref "U8") (pin "15") (pinfunction "SDA_15") (pintype "bidirectional"))
    )
    (net (code "19") (name "FLS1") (class "Default")
      (node (ref "IC6") (pin "2") (pinfunction "O_2") (pintype "output"))
      (node (ref "U7") (pin "3") (pinfunction "A1_3") (pintype "bidirectional"))
    )
    (net (code "20") (name "FLS2") (class "Default")
      (node (ref "IC6") (pin "4") (pinfunction "O_4") (pintype "output"))
      (node (ref "U7") (pin "4") (pinfunction "A2_4") (pintype "bidirectional"))
    )
    (net (code "21") (name "FLS3") (class "Default")
      (node (ref "IC6") (pin "6") (pinfunction "O_6") (pintype "output"))
      (node (ref "U7") (pin "9") (pinfunction "0_9") (pintype "bidirectional"))
    )
    (net (code "22") (name "FLS4") (class "Default")
      (node (ref "IC6") (pin "10") (pinfunction "O_10") (pintype "output"))
      (node (ref "U7") (pin "10") (pinfunction "1_10") (pintype "bidirectional"))
    )
    (net (code "23") (name "FLS5") (class "Default")
      (node (ref "IC6") (pin "12") (pinfunction "O_12") (pintype "output"))
      (node (ref "U7") (pin "13") (pinfunction "~{4}_13") (pintype "bidirectional"))
    )
    (net (code "24") (name "GND") (class "Default")
      (node (ref "B1") (pin "-") (pinfunction "-_-") (pintype "passive"))
      (node (ref "C1") (pin "-") (pinfunction "-_-") (pintype "passive"))
      (node (ref "C10") (pin "2") (pinfunction "2_2") (pintype "passive"))
      (node (ref "C2") (pin "2") (pinfunction "2_2") (pintype "passive"))
      (node (ref "C3") (pin "2") (pinfunction "2_2") (pintype "passive"))
      (node (ref "C5") (pin "2") (pinfunction "2_2") (pintype "passive"))
      (node (ref "C6") (pin "2") (pinfunction "2_2") (pintype "passive"))
      (node (ref "C8") (pin "2") (pinfunction "2_2") (pintype "passive"))
      (node (ref "C9") (pin "2") (pinfunction "2_2") (pintype "passive"))
      (node (ref "IC1") (pin "7") (pinfunction "GND_7") (pintype "power_in"))
      (node (ref "IC2") (pin "1") (pinfunction "GND_1") (pintype "passive"))
      (node (ref "IC2") (pin "4") (pinfunction "GND_4") (pintype "passive"))
      (node (ref "IC3") (pin "4") (pinfunction "P$V-_4") (pintype "bidirectional"))
      (node (ref "IC4") (pin "4") (pinfunction "P$V-_4") (pintype "bidirectional"))
      (node (ref "IC5") (pin "4") (pinfunction "P$V-_4") (pintype "bidirectional"))
      (node (ref "IC6") (pin "8") (pinfunction "VSS_8") (pintype "power_in"))
      (node (ref "IC7") (pin "1") (pinfunction "GND_1") (pintype "passive"))
      (node (ref "IC7") (pin "4") (pinfunction "GND_4") (pintype "passive"))
      (node (ref "IC8") (pin "1") (pinfunction "GND_1") (pintype "passive"))
      (node (ref "IC8") (pin "4") (pinfunction "GND_4") (pintype "passive"))
      (node (ref "J1") (pin "1") (pinfunction "1_1") (pintype "bidirectional"))
      (node (ref "J1") (pin "2") (pinfunction "2_2") (pintype "bidirectional"))
      (node (ref "J1") (pin "3") (pinfunction "3_3") (pintype "bidirectional"))
      (node (ref "J1") (pin "4") (pinfunction "4_4") (pintype "bidirectional"))
      (node (ref "J10") (pin "1") (pinfunction "1_1") (pintype "bidirectional"))
      (node (ref "J11") (pin "1") (pinfunction "1_1") (pintype "bidirectional"))
      (node (ref "J6") (pin "4") (pinfunction "4_4") (pintype "bidirectional"))
      (node (ref "J7") (pin "1") (pinfunction "1_1") (pintype "bidirectional"))
      (node (ref "J8") (pin "1") (pinfunction "1_1") (pintype "bidirectional"))
      (node (ref "J9") (pin "1") (pinfunction "1_1") (pintype "bidirectional"))
      (node (ref "JP1") (pin "10") (pinfunction "GND_10") (pintype "power_in"))
      (node (ref "J_BT_BOARD_1") (pin "GND") (pinfunction "GND_GND") (pintype "bidirectional"))
      (node (ref "LED1") (pin "C") (pinfunction "C_C") (pintype "passive"))
      (node (ref "Q1") (pin "2") (pinfunction "E_2") (pintype "passive"))
      (node (ref "Q2") (pin "2") (pinfunction "E_2") (pintype "passive"))
      (node (ref "Q3") (pin "2") (pinfunction "E_2") (pintype "passive"))
      (node (ref "Q4") (pin "2") (pinfunction "E_2") (pintype "passive"))
      (node (ref "Q5") (pin "2") (pinfunction "E_2") (pintype "passive"))
      (node (ref "R17") (pin "1") (pinfunction "1_1") (pintype "passive"))
      (node (ref "R18") (pin "1") (pinfunction "1_1") (pintype "passive"))
      (node (ref "R19") (pin "1") (pinfunction "1_1") (pintype "passive"))
      (node (ref "R20") (pin "1") (pinfunction "1_1") (pintype "passive"))
      (node (ref "R22") (pin "1") (pinfunction "1_1") (pintype "passive"))
      (node (ref "R24") (pin "1") (pinfunction "1_1") (pintype "passive"))
      (node (ref "R26") (pin "1") (pinfunction "1_1") (pintype "passive"))
      (node (ref "R28") (pin "1") (pinfunction "1_1") (pintype "passive"))
      (node (ref "R29") (pin "1") (pinfunction "A_1") (pintype "passive"))
      (node (ref "R35") (pin "1") (pinfunction "1_1") (pintype "passive"))
      (node (ref "R4") (pin "1") (pinfunction "1_1") (pintype "passive"))
      (node (ref "R5") (pin "1") (pinfunction "1_1") (pintype "passive"))
      (node (ref "R6") (pin "1") (pinfunction "1_1") (pintype "passive"))
      (node (ref "R7") (pin "1") (pinfunction "1_1") (pintype "passive"))
      (node (ref "R8") (pin "1") (pinfunction "1_1") (pintype "passive"))
      (node (ref "U1") (pin "1") (pinfunction "GND_1") (pintype "bidirectional"))
      (node (ref "U2") (pin "COM") (pinfunction "GND_COM") (pintype "bidirectional"))
      (node (ref "U3") (pin "2") (pinfunction "GND_2") (pintype "bidirectional"))
      (node (ref "U4") (pin "2") (pinfunction "GND_2") (pintype "bidirectional"))
      (node (ref "U5") (pin "2") (pinfunction "GND_2") (pintype "bidirectional"))
      (node (ref "U6") (pin "2") (pinfunction "GND_2") (pintype "bidirectional"))
      (node (ref "U7") (pin "25") (pinfunction "GND_25") (pintype "bidirectional"))
      (node (ref "U8") (pin "1") (pinfunction "A0_1") (pintype "bidirectional"))
      (node (ref "U8") (pin "2") (pinfunction "A1_2") (pintype "bidirectional"))
      (node (ref "U8") (pin "3") (pinfunction "A2_3") (pintype "bidirectional"))
      (node (ref "U8") (pin "8") (pinfunction "GND_8") (pintype "bidirectional"))
    )
    (net (code "25") (name "GPS_RX") (class "Default")
      (node (ref "J6") (pin "1") (pinfunction "1_1") (pintype "bidirectional"))
      (node (ref "U7") (pin "15") (pinfunction "6_15") (pintype "bidirectional"))
    )
    (net (code "26") (name "GPS_TX") (class "Default")
      (node (ref "J6") (pin "2") (pinfunction "2_2") (pintype "bidirectional"))
      (node (ref "U7") (pin "16") (pinfunction "7_16") (pintype "bidirectional"))
    )
    (net (code "27") (name "IN_LED2_ON") (class "Default")
      (node (ref "R37") (pin "1") (pinfunction "1_1") (pintype "passive"))
      (node (ref "U7") (pin "19") (pinfunction "10/MISO_19") (pintype "bidirectional"))
    )
    (net (code "28") (name "LED1") (class "Default")
      (node (ref "J1") (pin "12") (pinfunction "12_12") (pintype "bidirectional"))
      (node (ref "Q1") (pin "3") (pinfunction "C_3") (pintype "passive"))
    )
    (net (code "29") (name "LED1_ON") (class "Default")
      (node (ref "Q1") (pin "1") (pinfunction "B_1") (pintype "passive"))
      (node (ref "R13") (pin "1") (pinfunction "1_1") (pintype "passive"))
      (node (ref "R17") (pin "2") (pinfunction "2_2") (pintype "passive"))
    )
    (net (code "30") (name "LED2") (class "Default")
      (node (ref "J1") (pin "11") (pinfunction "11_11") (pintype "bidirectional"))
      (node (ref "Q2") (pin "3") (pinfunction "C_3") (pintype "passive"))
    )
    (net (code "31") (name "LED2_ON") (class "Default")
      (node (ref "Q2") (pin "1") (pinfunction "B_1") (pintype "passive"))
      (node (ref "R14") (pin "1") (pinfunction "1_1") (pintype "passive"))
      (node (ref "R18") (pin "2") (pinfunction "2_2") (pintype "passive"))
    )
    (net (code "32") (name "LED3") (class "Default")
      (node (ref "J1") (pin "10") (pinfunction "10_10") (pintype "bidirectional"))
      (node (ref "Q3") (pin "3") (pinfunction "C_3") (pintype "passive"))
    )
    (net (code "33") (name "LED3_ON") (class "Default")
      (node (ref "Q3") (pin "1") (pinfunction "B_1") (pintype "passive"))
      (node (ref "R15") (pin "1") (pinfunction "1_1") (pintype "passive"))
      (node (ref "R19") (pin "2") (pinfunction "2_2") (pintype "passive"))
    )
    (net (code "34") (name "LED4") (class "Default")
      (node (ref "J1") (pin "9") (pinfunction "9_9") (pintype "bidirectional"))
      (node (ref "Q4") (pin "3") (pinfunction "C_3") (pintype "passive"))
    )
    (net (code "35") (name "LED4_ON") (class "Default")
      (node (ref "Q4") (pin "1") (pinfunction "B_1") (pintype "passive"))
      (node (ref "R16") (pin "1") (pinfunction "1_1") (pintype "passive"))
      (node (ref "R20") (pin "2") (pinfunction "2_2") (pintype "passive"))
    )
    (net (code "36") (name "Net-(B1-AC2)") (class "Default")
      (node (ref "B1") (pin "AC1") (pinfunction "AC2_AC1") (pintype "passive"))
      (node (ref "T1") (pin "6") (pinfunction "6_6") (pintype "passive"))
      (node (ref "T1") (pin "8") (pinfunction "8_8") (pintype "passive"))
    )
    (net (code "37") (name "Net-(C7-Pad1)") (class "Default")
      (node (ref "C7") (pin "1") (pinfunction "1_1") (pintype "passive"))
      (node (ref "R2") (pin "1") (pinfunction "1_1") (pintype "passive"))
      (node (ref "R3") (pin "2") (pinfunction "2_2") (pintype "passive"))
    )
    (net (code "38") (name "Net-(C9-Pad1)") (class "Default")
      (node (ref "C9") (pin "1") (pinfunction "1_1") (pintype "passive"))
      (node (ref "FB1") (pin "1") (pinfunction "1_1") (pintype "passive"))
      (node (ref "U2") (pin "OUT") (pinfunction "OUT_OUT") (pintype "bidirectional"))
    )
    (net (code "39") (name "Net-(CONN_1-Pad1)") (class "Default")
      (node (ref "CONN_1") (pin "1") (pinfunction "1_1") (pintype "bidirectional"))
      (node (ref "F1") (pin "1") (pinfunction "1_1") (pintype "passive"))
    )
    (net (code "40") (name "Net-(CONN_1-Pad2)") (class "Default")
      (node (ref "CONN_1") (pin "2") (pinfunction "2_2") (pintype "bidirectional"))
      (node (ref "F2") (pin "1") (pinfunction "1_1") (pintype "passive"))
    )
    (net (code "41") (name "Net-(F1-Pad2)") (class "Default")
      (node (ref "F1") (pin "2") (pinfunction "2_2") (pintype "passive"))
      (node (ref "T1") (pin "1") (pinfunction "1_1") (pintype "passive"))
      (node (ref "T1") (pin "4") (pinfunction "4_4") (pintype "passive"))
    )
    (net (code "42") (name "Net-(F2-Pad2)") (class "Default")
      (node (ref "F2") (pin "2") (pinfunction "2_2") (pintype "passive"))
      (node (ref "T1") (pin "2") (pinfunction "2_2") (pintype "passive"))
      (node (ref "T1") (pin "3") (pinfunction "3_3") (pintype "passive"))
    )
    (net (code "43") (name "Net-(IC1A-I1)") (class "Default")
      (node (ref "IC1") (pin "2") (pinfunction "I1_2") (pintype "input"))
      (node (ref "U3") (pin "5") (pinfunction "OUT_5") (pintype "bidirectional"))
    )
    (net (code "44") (name "Net-(IC1A-O)") (class "Default")
      (node (ref "IC1") (pin "3") (pinfunction "O_3") (pintype "output"))
      (node (ref "IC7") (pin "5") (pinfunction "VIN_5") (pintype "passive"))
      (node (ref "R13") (pin "2") (pinfunction "2_2") (pintype "passive"))
      (node (ref "R21") (pin "2") (pinfunction "2_2") (pintype "passive"))
    )
    (net (code "45") (name "Net-(IC1B-I1)") (class "Default")
      (node (ref "IC1") (pin "5") (pinfunction "I1_5") (pintype "input"))
      (node (ref "U4") (pin "5") (pinfunction "OUT_5") (pintype "bidirectional"))
    )
    (net (code "46") (name "Net-(IC1B-O)") (class "Default")
      (node (ref "IC1") (pin "6") (pinfunction "O_6") (pintype "output"))
      (node (ref "IC7") (pin "2") (pinfunction "VIN_2") (pintype "passive"))
      (node (ref "R14") (pin "2") (pinfunction "2_2") (pintype "passive"))
      (node (ref "R23") (pin "2") (pinfunction "2_2") (pintype "passive"))
    )
    (net (code "47") (name "Net-(IC1C-I1)") (class "Default")
      (node (ref "IC1") (pin "10") (pinfunction "I1_10") (pintype "input"))
      (node (ref "U5") (pin "5") (pinfunction "OUT_5") (pintype "bidirectional"))
    )
    (net (code "48") (name "Net-(IC1C-O)") (class "Default")
      (node (ref "IC1") (pin "8") (pinfunction "O_8") (pintype "output"))
      (node (ref "IC2") (pin "5") (pinfunction "VIN_5") (pintype "passive"))
      (node (ref "R15") (pin "2") (pinfunction "2_2") (pintype "passive"))
      (node (ref "R25") (pin "2") (pinfunction "2_2") (pintype "passive"))
    )
    (net (code "49") (name "Net-(IC1D-I1)") (class "Default")
      (node (ref "IC1") (pin "13") (pinfunction "I1_13") (pintype "input"))
      (node (ref "U6") (pin "5") (pinfunction "OUT_5") (pintype "bidirectional"))
    )
    (net (code "50") (name "Net-(IC1D-O)") (class "Default")
      (node (ref "IC1") (pin "11") (pinfunction "O_11") (pintype "output"))
      (node (ref "IC2") (pin "2") (pinfunction "VIN_2") (pintype "passive"))
      (node (ref "R16") (pin "2") (pinfunction "2_2") (pintype "passive"))
      (node (ref "R27") (pin "2") (pinfunction "2_2") (pintype "passive"))
    )
    (net (code "51") (name "Net-(IC2A-VOUT)") (class "Default")
      (node (ref "IC2") (pin "6") (pinfunction "VOUT_6") (pintype "passive"))
      (node (ref "K3") (pin "9") (pinfunction "2_9") (pintype "passive"))
    )
    (net (code "52") (name "Net-(IC2B-VOUT)") (class "Default")
      (node (ref "IC2") (pin "3") (pinfunction "VOUT_3") (pintype "passive"))
      (node (ref "K4") (pin "9") (pinfunction "2_9") (pintype "passive"))
    )
    (net (code "53") (name "Net-(IC3A-+IN)") (class "Default")
      (node (ref "IC3") (pin "3") (pinfunction "+IN_3") (pintype "input"))
      (node (ref "J7") (pin "2") (pinfunction "2_2") (pintype "bidirectional"))
      (node (ref "R30") (pin "1") (pinfunction "1_1") (pintype "passive"))
    )
    (net (code "54") (name "Net-(IC3A--IN)") (class "Default")
      (node (ref "IC3") (pin "2") (pinfunction "-IN_2") (pintype "input"))
      (node (ref "IC3") (pin "6") (pinfunction "-IN_6") (pintype "input"))
      (node (ref "IC4") (pin "2") (pinfunction "-IN_2") (pintype "input"))
      (node (ref "IC4") (pin "6") (pinfunction "-IN_6") (pintype "input"))
      (node (ref "IC5") (pin "2") (pinfunction "-IN_2") (pintype "input"))
      (node (ref "R29") (pin "2") (pinfunction "S_2") (pintype "passive"))
    )
    (net (code "55") (name "Net-(IC3A-OUT)") (class "Default")
      (node (ref "IC3") (pin "1") (pinfunction "OUT_1") (pintype "output"))
      (node (ref "IC6") (pin "3") (pinfunction "I_3") (pintype "input"))
    )
    (net (code "56") (name "Net-(IC3B-+IN)") (class "Default")
      (node (ref "IC3") (pin "5") (pinfunction "+IN_5") (pintype "input"))
      (node (ref "J8") (pin "2") (pinfunction "2_2") (pintype "bidirectional"))
      (node (ref "R31") (pin "1") (pinfunction "1_1") (pintype "passive"))
    )
    (net (code "57") (name "Net-(IC3B-OUT)") (class "Default")
      (node (ref "IC3") (pin "7") (pinfunction "OUT_7") (pintype "output"))
      (node (ref "IC6") (pin "5") (pinfunction "I_5") (pintype "input"))
    )
    (net (code "58") (name "Net-(IC4A-+IN)") (class "Default")
      (node (ref "IC4") (pin "3") (pinfunction "+IN_3") (pintype "input"))
      (node (ref "J9") (pin "2") (pinfunction "2_2") (pintype "bidirectional"))
      (node (ref "R32") (pin "1") (pinfunction "1_1") (pintype "passive"))
    )
    (net (code "59") (name "Net-(IC4A-OUT)") (class "Default")
      (node (ref "IC4") (pin "1") (pinfunction "OUT_1") (pintype "output"))
      (node (ref "IC6") (pin "7") (pinfunction "I_7") (pintype "input"))
    )
    (net (code "60") (name "Net-(IC4B-+IN)") (class "Default")
      (node (ref "IC4") (pin "5") (pinfunction "+IN_5") (pintype "input"))
      (node (ref "J10") (pin "2") (pinfunction "2_2") (pintype "bidirectional"))
      (node (ref "R33") (pin "1") (pinfunction "1_1") (pintype "passive"))
    )
    (net (code "61") (name "Net-(IC4B-OUT)") (class "Default")
      (node (ref "IC4") (pin "7") (pinfunction "OUT_7") (pintype "output"))
      (node (ref "IC6") (pin "9") (pinfunction "I_9") (pintype "input"))
    )
    (net (code "62") (name "Net-(IC5A-+IN)") (class "Default")
      (node (ref "IC5") (pin "3") (pinfunction "+IN_3") (pintype "input"))
      (node (ref "J11") (pin "2") (pinfunction "2_2") (pintype "bidirectional"))
      (node (ref "R34") (pin "1") (pinfunction "1_1") (pintype "passive"))
    )
    (net (code "63") (name "Net-(IC5A-OUT)") (class "Default")
      (node (ref "IC5") (pin "1") (pinfunction "OUT_1") (pintype "output"))
      (node (ref "IC6") (pin "11") (pinfunction "I_11") (pintype "input"))
    )
    (net (code "64") (name "Net-(IC7A-VOUT)") (class "Default")
      (node (ref "IC7") (pin "6") (pinfunction "VOUT_6") (pintype "passive"))
      (node (ref "K1") (pin "9") (pinfunction "2_9") (pintype "passive"))
    )
    (net (code "65") (name "Net-(IC7B-VOUT)") (class "Default")
      (node (ref "IC7") (pin "3") (pinfunction "VOUT_3") (pintype "passive"))
      (node (ref "K2") (pin "9") (pinfunction "2_9") (pintype "passive"))
    )
    (net (code "66") (name "Net-(IC8A-VOUT)") (class "Default")
      (node (ref "IC8") (pin "6") (pinfunction "VOUT_6") (pintype "passive"))
      (node (ref "K5") (pin "9") (pinfunction "2_9") (pintype "passive"))
    )
    (net (code "67") (name "Net-(IC8B-VOUT)") (class "Default")
      (node (ref "IC8") (pin "3") (pinfunction "VOUT_3") (pintype "passive"))
      (node (ref "K6") (pin "9") (pinfunction "2_9") (pintype "passive"))
    )
    (net (code "68") (name "Net-(J12-Pad1)") (class "Default")
      (node (ref "J12") (pin "1") (pinfunction "1_1") (pintype "bidirectional"))
      (node (ref "JP2") (pin "2") (pinfunction "2_2") (pintype "passive"))
    )
    (net (code "69") (name "Net-(J12-Pad2)") (class "Default")
      (node (ref "J12") (pin "2") (pinfunction "2_2") (pintype "bidirectional"))
      (node (ref "K5") (pin "5") (pinfunction "P_5") (pintype "passive"))
      (node (ref "K5") (pin "6") (pinfunction "P_6") (pintype "passive"))
    )
    (net (code "70") (name "Net-(J13-Pad1)") (class "Default")
      (node (ref "J13") (pin "1") (pinfunction "1_1") (pintype "bidirectional"))
      (node (ref "JP3") (pin "2") (pinfunction "2_2") (pintype "passive"))
    )
    (net (code "71") (name "Net-(J13-Pad2)") (class "Default")
      (node (ref "J13") (pin "2") (pinfunction "2_2") (pintype "bidirectional"))
      (node (ref "K6") (pin "5") (pinfunction "P_5") (pintype "passive"))
      (node (ref "K6") (pin "6") (pinfunction "P_6") (pintype "passive"))
    )
    (net (code "72") (name "Net-(K1B-S)") (class "Default")
      (node (ref "J2") (pin "2") (pinfunction "2_2") (pintype "bidirectional"))
      (node (ref "K1") (pin "10") (pinfunction "S_10") (pintype "passive"))
    )
    (net (code "73") (name "Net-(K2B-S)") (class "Default")
      (node (ref "J3") (pin "2") (pinfunction "2_2") (pintype "bidirectional"))
      (node (ref "K2") (pin "10") (pinfunction "S_10") (pintype "passive"))
    )
    (net (code "74") (name "Net-(K3B-S)") (class "Default")
      (node (ref "J4") (pin "2") (pinfunction "2_2") (pintype "bidirectional"))
      (node (ref "K3") (pin "10") (pinfunction "S_10") (pintype "passive"))
    )
    (net (code "75") (name "Net-(K4B-S)") (class "Default")
      (node (ref "J5") (pin "2") (pinfunction "2_2") (pintype "bidirectional"))
      (node (ref "K4") (pin "10") (pinfunction "S_10") (pintype "passive"))
    )
    (net (code "76") (name "Net-(K5B-O)") (class "Default")
      (node (ref "JP2") (pin "3") (pinfunction "3_3") (pintype "passive"))
      (node (ref "K5") (pin "1") (pinfunction "O_1") (pintype "passive"))
    )
    (net (code "77") (name "Net-(K5B-S)") (class "Default")
      (node (ref "JP2") (pin "1") (pinfunction "1_1") (pintype "passive"))
      (node (ref "K5") (pin "10") (pinfunction "S_10") (pintype "passive"))
    )
    (net (code "78") (name "Net-(K6B-O)") (class "Default")
      (node (ref "JP3") (pin "3") (pinfunction "3_3") (pintype "passive"))
      (node (ref "K6") (pin "1") (pinfunction "O_1") (pintype "passive"))
    )
    (net (code "79") (name "Net-(K6B-S)") (class "Default")
      (node (ref "JP3") (pin "1") (pinfunction "1_1") (pintype "passive"))
      (node (ref "K6") (pin "10") (pinfunction "S_10") (pintype "passive"))
    )
    (net (code "80") (name "Net-(LED1-PadA)") (class "Default")
      (node (ref "LED1") (pin "A") (pinfunction "A_A") (pintype "passive"))
      (node (ref "R41") (pin "1") (pinfunction "1_1") (pintype "passive"))
    )
    (net (code "81") (name "Net-(LED2-PadA)") (class "Default")
      (node (ref "LED2") (pin "A") (pinfunction "A_A") (pintype "passive"))
      (node (ref "R36") (pin "1") (pinfunction "1_1") (pintype "passive"))
    )
    (net (code "82") (name "Net-(Q5-B)") (class "Default")
      (node (ref "Q5") (pin "1") (pinfunction "B_1") (pintype "passive"))
      (node (ref "R35") (pin "2") (pinfunction "2_2") (pintype "passive"))
      (node (ref "R37") (pin "2") (pinfunction "2_2") (pintype "passive"))
    )
    (net (code "83") (name "Net-(Q5-C)") (class "Default")
      (node (ref "LED2") (pin "C") (pinfunction "C_C") (pintype "passive"))
      (node (ref "Q5") (pin "3") (pinfunction "C_3") (pintype "passive"))
    )
    (net (code "84") (name "Net-(U1-BOOT)") (class "Default")
      (node (ref "C4") (pin "1") (pinfunction "1_1") (pintype "passive"))
      (node (ref "U1") (pin "6") (pinfunction "BOOT_6") (pintype "bidirectional"))
    )
    (net (code "85") (name "Net-(U1-EN)") (class "Default")
      (node (ref "R1") (pin "2") (pinfunction "2_2") (pintype "passive"))
      (node (ref "U1") (pin "5") (pinfunction "EN_5") (pintype "bidirectional"))
    )
    (net (code "86") (name "Net-(U1-FB)") (class "Default")
      (node (ref "C7") (pin "2") (pinfunction "2_2") (pintype "passive"))
      (node (ref "R3") (pin "1") (pinfunction "1_1") (pintype "passive"))
      (node (ref "R4") (pin "2") (pinfunction "2_2") (pintype "passive"))
      (node (ref "U1") (pin "4") (pinfunction "FB_4") (pintype "bidirectional"))
    )
    (net (code "87") (name "Net-(U1-SW)") (class "Default")
      (node (ref "C4") (pin "2") (pinfunction "2_2") (pintype "passive"))
      (node (ref "L1") (pin "1") (pinfunction "1_1") (pintype "passive"))
      (node (ref "U1") (pin "2") (pinfunction "SW_2") (pintype "bidirectional"))
    )
    (net (code "88") (name "PUMP_OFF") (class "Default")
      (node (ref "IC8") (pin "2") (pinfunction "VIN_2") (pintype "passive"))
      (node (ref "U7") (pin "12") (pinfunction "~{3}_12") (pintype "bidirectional"))
    )
    (net (code "89") (name "PUMP_ON") (class "Default")
      (node (ref "IC8") (pin "5") (pinfunction "VIN_5") (pintype "passive"))
      (node (ref "U7") (pin "11") (pinfunction "~{2}_11") (pintype "bidirectional"))
    )
    (net (code "90") (name "V1_FB") (class "Default")
      (node (ref "R21") (pin "1") (pinfunction "1_1") (pintype "passive"))
      (node (ref "R22") (pin "2") (pinfunction "2_2") (pintype "passive"))
      (node (ref "U8") (pin "12") (pinfunction "P7_12") (pintype "bidirectional"))
    )
    (net (code "91") (name "V2_FB") (class "Default")
      (node (ref "R23") (pin "1") (pinfunction "1_1") (pintype "passive"))
      (node (ref "R24") (pin "2") (pinfunction "2_2") (pintype "passive"))
      (node (ref "U8") (pin "10") (pinfunction "P5_10") (pintype "bidirectional"))
    )
    (net (code "92") (name "V3_FB") (class "Default")
      (node (ref "R25") (pin "1") (pinfunction "1_1") (pintype "passive"))
      (node (ref "R26") (pin "2") (pinfunction "2_2") (pintype "passive"))
      (node (ref "U8") (pin "11") (pinfunction "P6_11") (pintype "bidirectional"))
    )
    (net (code "93") (name "V4_FB") (class "Default")
      (node (ref "R27") (pin "1") (pinfunction "1_1") (pintype "passive"))
      (node (ref "R28") (pin "2") (pinfunction "2_2") (pintype "passive"))
      (node (ref "U8") (pin "9") (pinfunction "P4_9") (pintype "bidirectional"))
    )
    (net (code "94") (name "VDIG1") (class "Default")
      (node (ref "IC1") (pin "1") (pinfunction "I0_1") (pintype "input"))
      (node (ref "U7") (pin "6") (pinfunction "A4_6") (pintype "bidirectional"))
    )
    (net (code "95") (name "VDIG2") (class "Default")
      (node (ref "IC1") (pin "4") (pinfunction "I0_4") (pintype "input"))
      (node (ref "U7") (pin "5") (pinfunction "A3_5") (pintype "bidirectional"))
    )
    (net (code "96") (name "VDIG3") (class "Default")
      (node (ref "IC1") (pin "9") (pinfunction "I0_9") (pintype "input"))
      (node (ref "U7") (pin "8") (pinfunction "A6_8") (pintype "bidirectional"))
    )
    (net (code "97") (name "VDIG4") (class "Default")
      (node (ref "IC1") (pin "12") (pinfunction "I0_12") (pintype "input"))
      (node (ref "U7") (pin "7") (pinfunction "A5_7") (pintype "bidirectional"))
    )
    (net (code "98") (name "XB_RX") (class "Default")
      (node (ref "JP1") (pin "3") (pinfunction "DIN_3") (pintype "input"))
      (node (ref "U7") (pin "17") (pinfunction "8/MOSI_17") (pintype "bidirectional"))
    )
    (net (code "99") (name "XB_TX") (class "Default")
      (node (ref "JP1") (pin "2") (pinfunction "DOUT_2") (pintype "output"))
      (node (ref "U7") (pin "18") (pinfunction "9/SCK_18") (pintype "bidirectional"))
    )
    (net (code "100") (name "unconnected-(JP1-CTS-Pad12)") (class "Default")
      (node (ref "JP1") (pin "12") (pinfunction "CTS_12") (pintype "output"))
    )
    (net (code "101") (name "unconnected-(JP1-DIO0-Pad20)") (class "Default")
      (node (ref "JP1") (pin "20") (pinfunction "DIO0_20") (pintype "bidirectional"))
    )
    (net (code "102") (name "unconnected-(JP1-DIO1-Pad19)") (class "Default")
      (node (ref "JP1") (pin "19") (pinfunction "DIO1_19") (pintype "bidirectional"))
    )
    (net (code "103") (name "unconnected-(JP1-DIO2-Pad18)") (class "Default")
      (node (ref "JP1") (pin "18") (pinfunction "DIO2_18") (pintype "bidirectional"))
    )
    (net (code "104") (name "unconnected-(JP1-DIO3-Pad17)") (class "Default")
      (node (ref "JP1") (pin "17") (pinfunction "DIO3_17") (pintype "bidirectional"))
    )
    (net (code "105") (name "unconnected-(JP1-DIO4-Pad11)") (class "Default")
      (node (ref "JP1") (pin "11") (pinfunction "DIO4_11") (pintype "bidirectional"))
    )
    (net (code "106") (name "unconnected-(JP1-DIO5-Pad15)") (class "Default")
      (node (ref "JP1") (pin "15") (pinfunction "DIO5_15") (pintype "bidirectional"))
    )
    (net (code "107") (name "unconnected-(JP1-DIO9-Pad13)") (class "Default")
      (node (ref "JP1") (pin "13") (pinfunction "DIO9_13") (pintype "bidirectional"))
    )
    (net (code "108") (name "unconnected-(JP1-DIO11-Pad7)") (class "Default")
      (node (ref "JP1") (pin "7") (pinfunction "DIO11_7") (pintype "bidirectional"))
    )
    (net (code "109") (name "unconnected-(JP1-DIO12-Pad4)") (class "Default")
      (node (ref "JP1") (pin "4") (pinfunction "DIO12_4") (pintype "bidirectional"))
    )
    (net (code "110") (name "unconnected-(JP1-DTR-Pad9)") (class "Default")
      (node (ref "JP1") (pin "9") (pinfunction "DTR_9") (pintype "bidirectional"))
    )
    (net (code "111") (name "unconnected-(JP1-RES-Pad8)") (class "Default")
      (node (ref "JP1") (pin "8") (pinfunction "RES_8") (pintype "bidirectional"))
    )
    (net (code "112") (name "unconnected-(JP1-RES-Pad14)") (class "Default")
      (node (ref "JP1") (pin "14") (pinfunction "RES_14") (pintype "bidirectional"))
    )
    (net (code "113") (name "unconnected-(JP1-RESET-Pad5)") (class "Default")
      (node (ref "JP1") (pin "5") (pinfunction "RESET_5") (pintype "input"))
    )
    (net (code "114") (name "unconnected-(JP1-RSSI-Pad6)") (class "Default")
      (node (ref "JP1") (pin "6") (pinfunction "RSSI_6") (pintype "bidirectional"))
    )
    (net (code "115") (name "unconnected-(JP1-RTS-Pad16)") (class "Default")
      (node (ref "JP1") (pin "16") (pinfunction "RTS_16") (pintype "input"))
    )
    (net (code "116") (name "unconnected-(K1B-O-Pad1)") (class "Default")
      (node (ref "K1") (pin "1") (pinfunction "O_1") (pintype "passive"))
    )
    (net (code "117") (name "unconnected-(K2B-O-Pad1)") (class "Default")
      (node (ref "K2") (pin "1") (pinfunction "O_1") (pintype "passive"))
    )
    (net (code "118") (name "unconnected-(K3B-O-Pad1)") (class "Default")
      (node (ref "K3") (pin "1") (pinfunction "O_1") (pintype "passive"))
    )
    (net (code "119") (name "unconnected-(K4B-O-Pad1)") (class "Default")
      (node (ref "K4") (pin "1") (pinfunction "O_1") (pintype "passive"))
    )
    (net (code "120") (name "unconnected-(U3-~{OUT}-Pad4)") (class "Default")
      (node (ref "U3") (pin "4") (pinfunction "~{OUT}_4") (pintype "bidirectional"))
    )
    (net (code "121") (name "unconnected-(U4-~{OUT}-Pad4)") (class "Default")
      (node (ref "U4") (pin "4") (pinfunction "~{OUT}_4") (pintype "bidirectional"))
    )
    (net (code "122") (name "unconnected-(U5-~{OUT}-Pad4)") (class "Default")
      (node (ref "U5") (pin "4") (pinfunction "~{OUT}_4") (pintype "bidirectional"))
    )
    (net (code "123") (name "unconnected-(U6-~{OUT}-Pad4)") (class "Default")
      (node (ref "U6") (pin "4") (pinfunction "~{OUT}_4") (pintype "bidirectional"))
    )
    (net (code "124") (name "unconnected-(U7-5V-Pad28)") (class "Default")
      (node (ref "U7") (pin "28") (pinfunction "5V_28") (pintype "bidirectional"))
    )
    (net (code "125") (name "unconnected-(U7-AREF-Pad1)") (class "Default")
      (node (ref "U7") (pin "1") (pinfunction "AREF_1") (pintype "bidirectional"))
    )
    (net (code "126") (name "unconnected-(U7-DAC0{slash}A0-Pad2)") (class "Default")
      (node (ref "U7") (pin "2") (pinfunction "DAC0/A0_2") (pintype "bidirectional"))
    )
    (net (code "127") (name "unconnected-(U7-RESET-Pad24)") (class "Default")
      (node (ref "U7") (pin "24") (pinfunction "RESET_24") (pintype "bidirectional"))
    )
    (net (code "128") (name "unconnected-(U7-VCC-Pad26)") (class "Default")
      (node (ref "U7") (pin "26") (pinfunction "VCC_26") (pintype "bidirectional"))
    )
  )
)
